# MAIN.net
KiCad netlist of a schematic drawn in Altium Designer
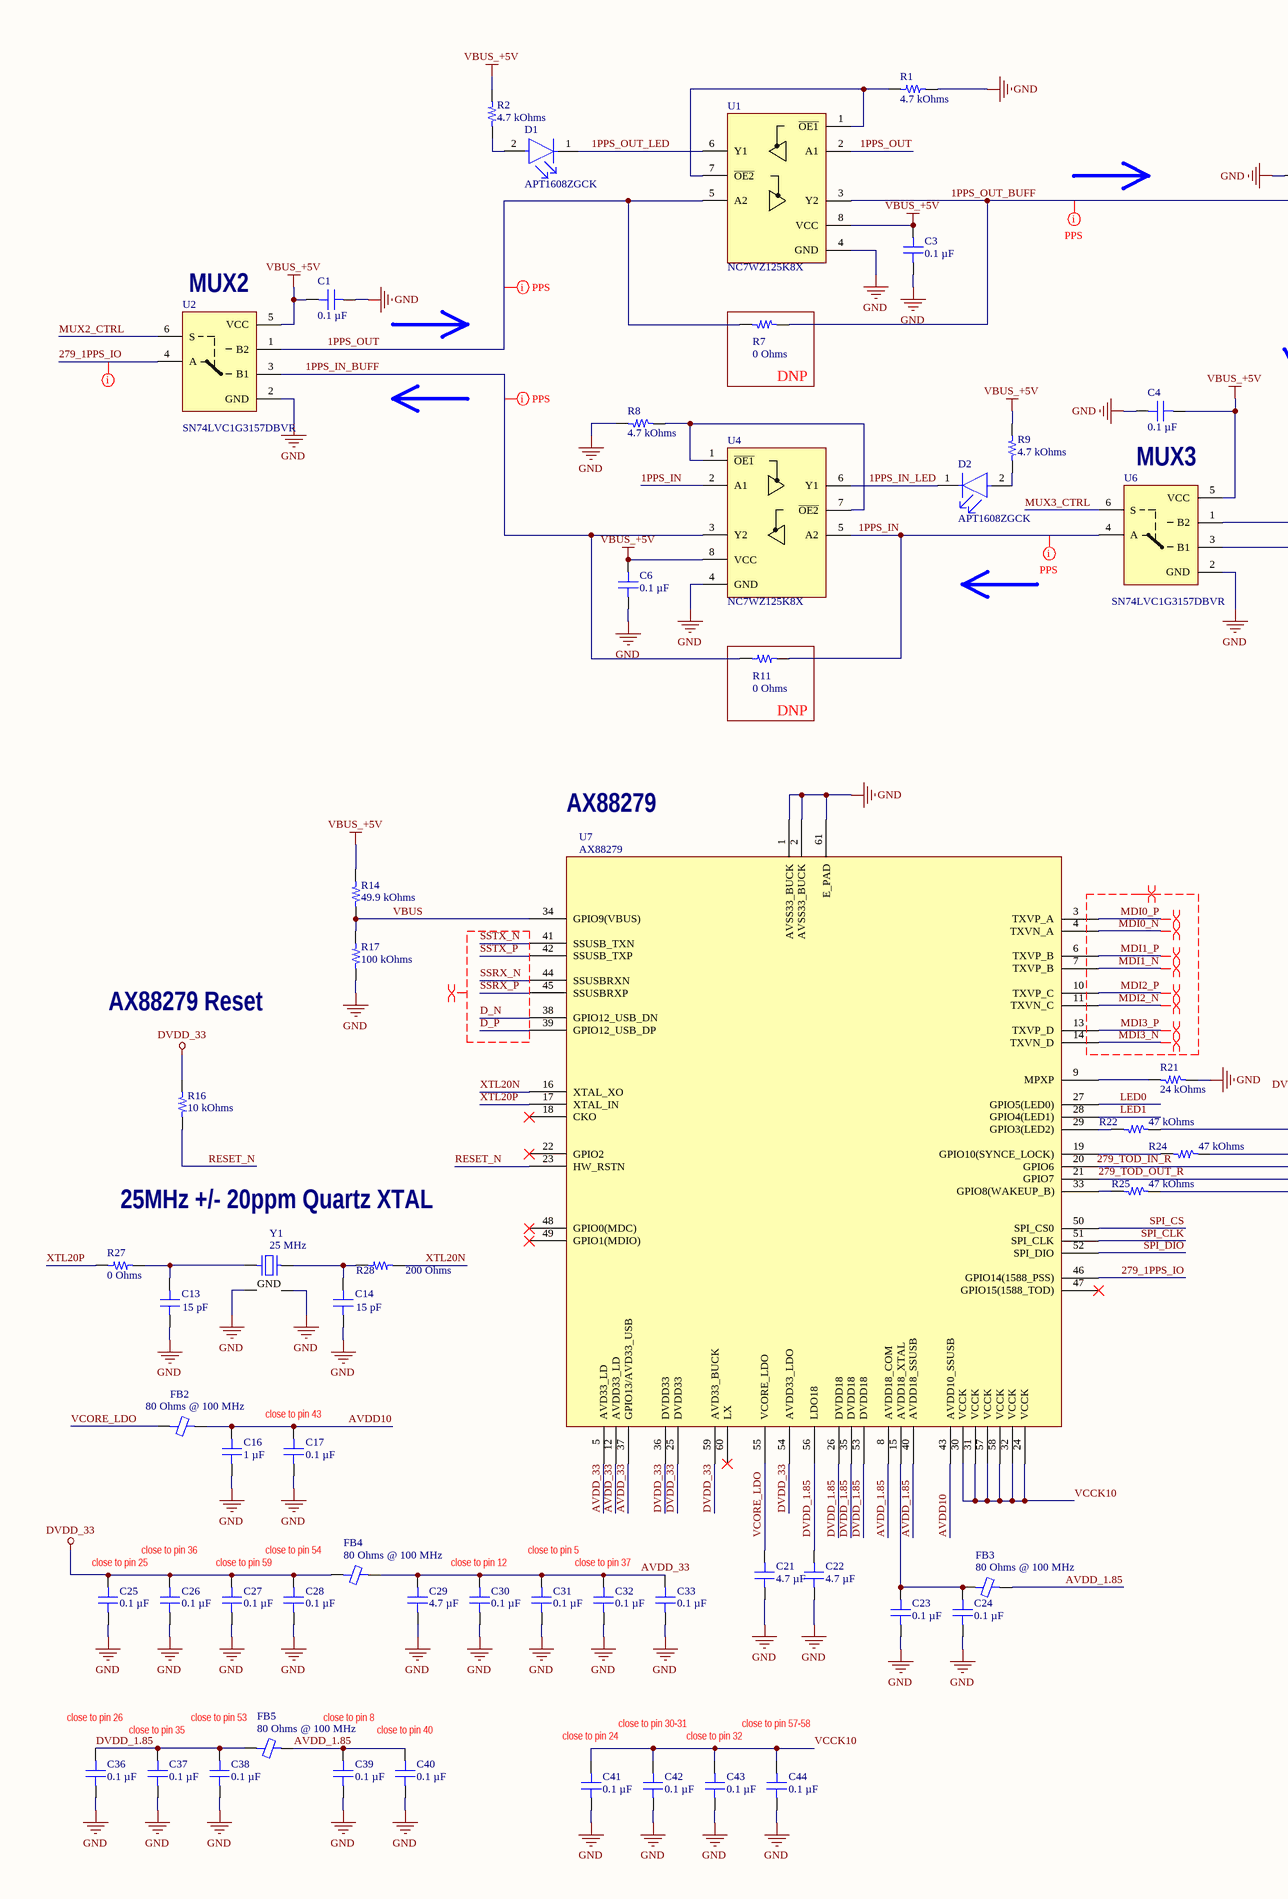
[diagram p0: MAIN.SchDoc, left]
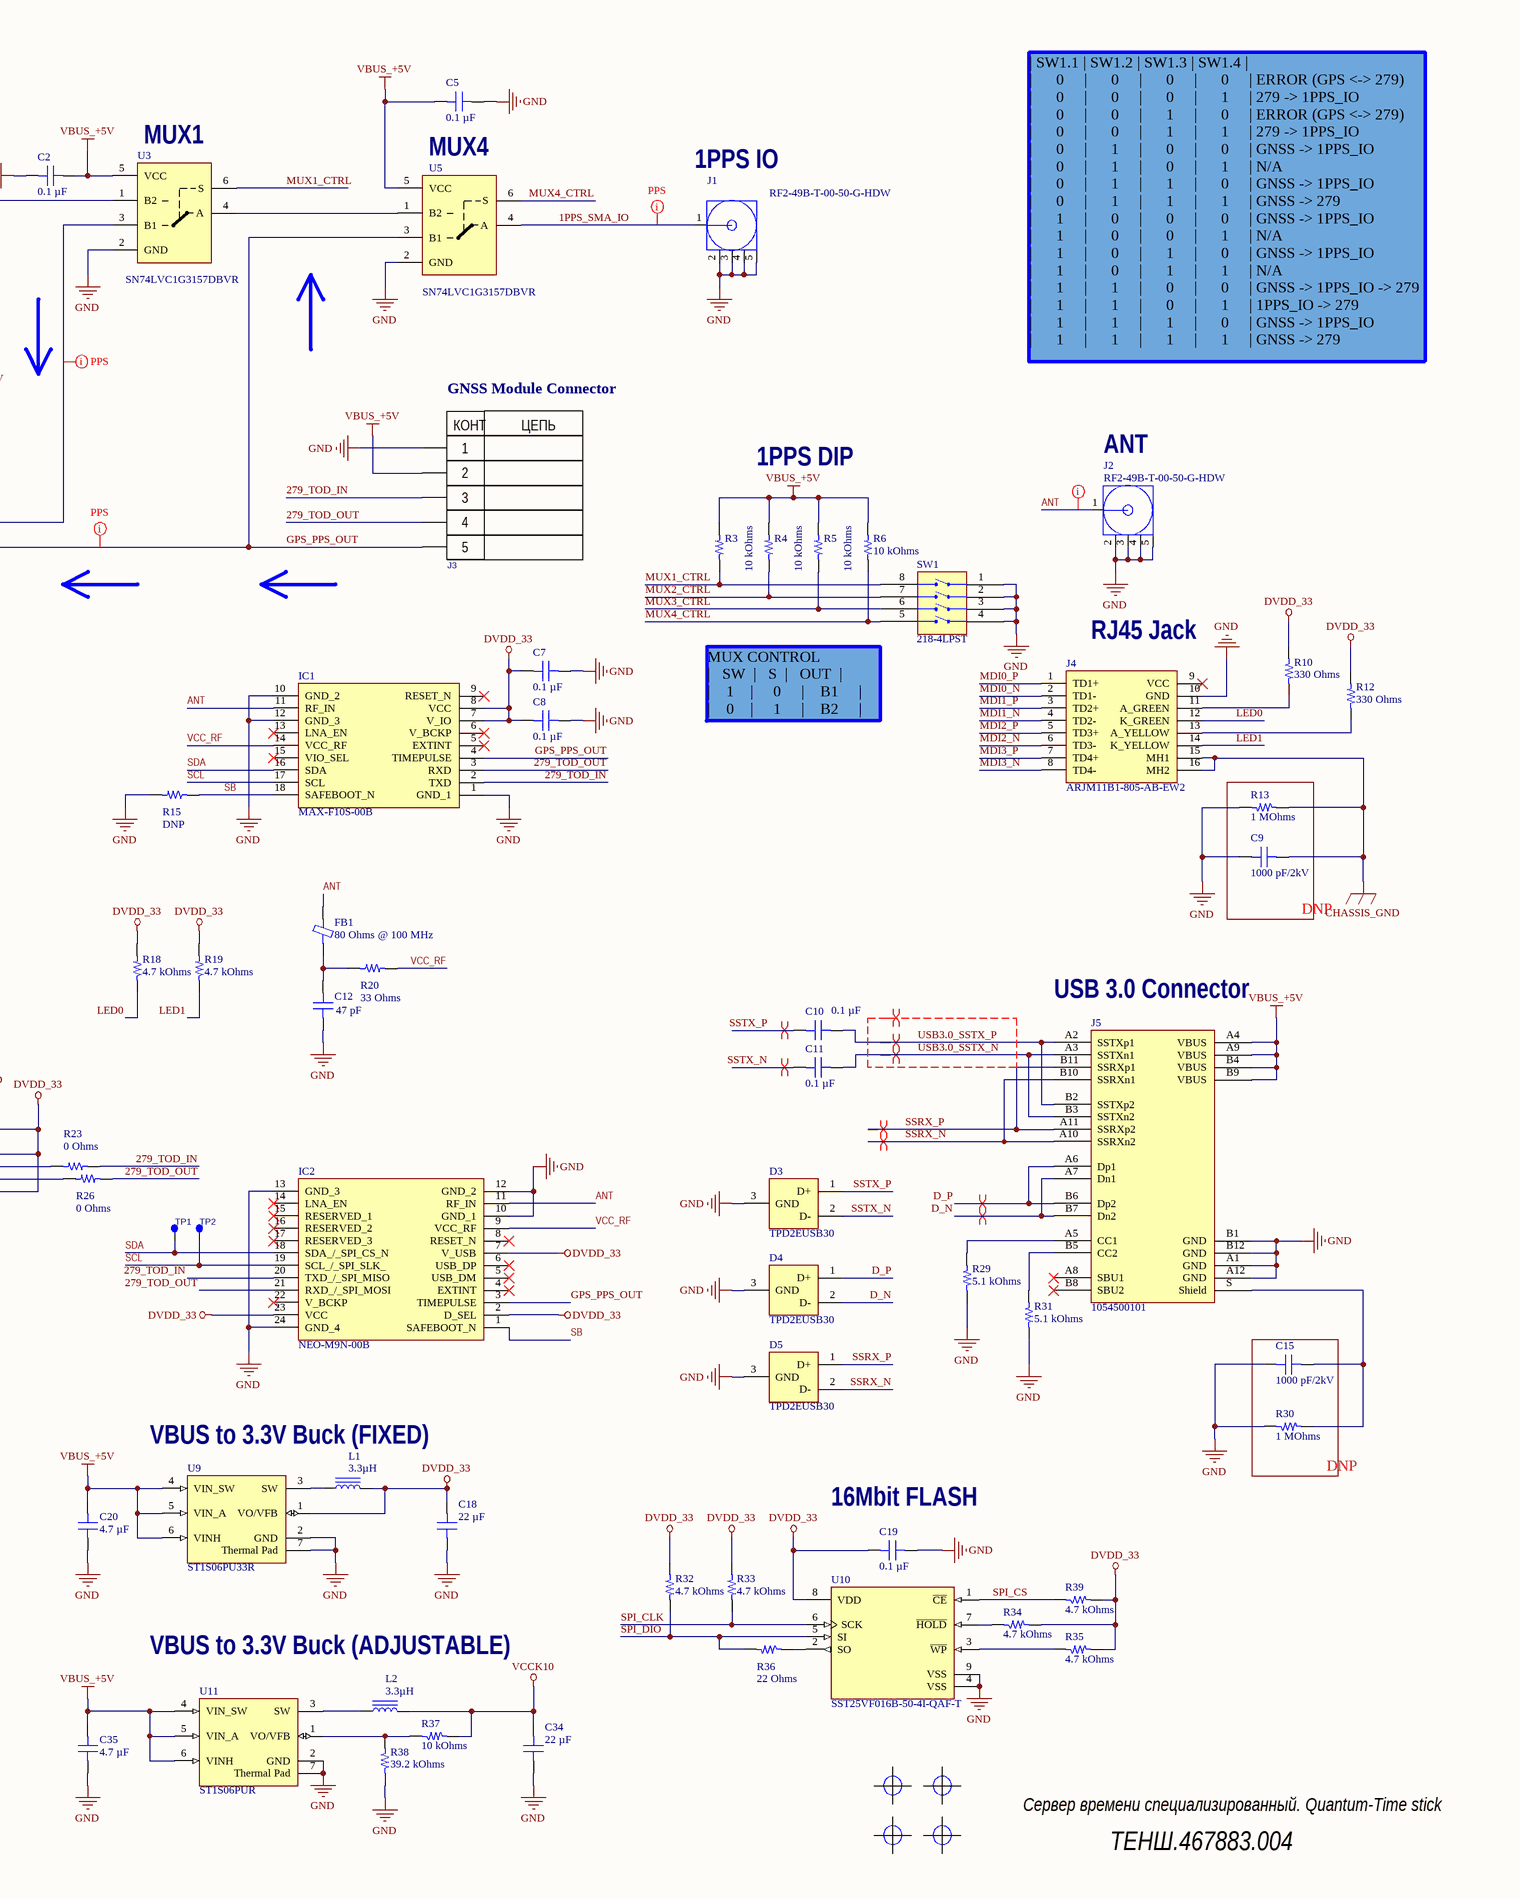
[diagram p1: MAIN.SchDoc, right]

(export (version "E")
  (design (tool "Eeschema 10.0.6"))
  (components
    (comp (ref "C1")
      (value "0.1 µF")
      (footprint "CAP 0402_1005")
      (description "CAP CER 0.1UF 10V X7R 0402")
      (fields (field (name "TOLERANCE") "±10%") (field (name "MANUFACTURER") "Yageo"))
      (libsource (lib "Celestial Altium Library - altium_library") (part "Capacitor"))
    )
    (comp (ref "C2")
      (value "0.1 µF")
      (footprint "CAP 0402_1005")
      (description "CAP CER 0.1UF 10V X7R 0402")
      (fields (field (name "TOLERANCE") "±10%") (field (name "MANUFACTURER") "Yageo"))
      (libsource (lib "Celestial Altium Library - altium_library") (part "Capacitor"))
    )
    (comp (ref "C3")
      (value "0.1 µF")
      (footprint "CAP 0402_1005")
      (description "CAP CER 0.1UF 10V X7R 0402")
      (fields (field (name "TOLERANCE") "±10%") (field (name "MANUFACTURER") "Yageo"))
      (libsource (lib "Celestial Altium Library - altium_library") (part "Capacitor"))
    )
    (comp (ref "C4")
      (value "0.1 µF")
      (footprint "CAP 0402_1005")
      (description "CAP CER 0.1UF 10V X7R 0402")
      (fields (field (name "TOLERANCE") "±10%") (field (name "MANUFACTURER") "Yageo"))
      (libsource (lib "Celestial Altium Library - altium_library") (part "Capacitor"))
    )
    (comp (ref "C5")
      (value "0.1 µF")
      (footprint "CAP 0402_1005")
      (description "CAP CER 0.1UF 10V X7R 0402")
      (fields (field (name "TOLERANCE") "±10%") (field (name "MANUFACTURER") "Yageo"))
      (libsource (lib "Celestial Altium Library - altium_library") (part "Capacitor"))
    )
    (comp (ref "C6")
      (value "0.1 µF")
      (footprint "CAP 0402_1005")
      (description "CAP CER 0.1UF 10V X7R 0402")
      (fields (field (name "TOLERANCE") "±10%") (field (name "MANUFACTURER") "Yageo"))
      (libsource (lib "Celestial Altium Library - altium_library") (part "Capacitor"))
    )
    (comp (ref "C7")
      (value "0.1 µF")
      (footprint "CAP 0402_1005")
      (description "CAP CER 0.1UF 10V X7R 0402")
      (fields (field (name "TOLERANCE") "±10%") (field (name "MANUFACTURER") "Yageo"))
      (libsource (lib "Celestial Altium Library - altium_library") (part "Capacitor"))
    )
    (comp (ref "C8")
      (value "0.1 µF")
      (footprint "CAP 0402_1005")
      (description "CAP CER 0.1UF 10V X7R 0402")
      (fields (field (name "TOLERANCE") "±10%") (field (name "MANUFACTURER") "Yageo"))
      (libsource (lib "Celestial Altium Library - altium_library") (part "Capacitor"))
    )
    (comp (ref "C9")
      (value "1000 pF/2kV")
      (footprint "CAP 1206_3216 - 0.8MM")
      (description "CAP CER 1000PF 2KV X7R 1206")
      (fields (field (name "PART NUMBER") "CC1206KKX7RDBB102") (field (name "MANUFACTURER") "Yageo"))
      (libsource (lib "Celestial Altium Library - altium_library") (part "Capacitor"))
    )
    (comp (ref "C10")
      (value "0.1 µF")
      (footprint "CAP 0402_1005")
      (description "CAP CER 0.1UF 10V X7R 0402")
      (fields (field (name "TOLERANCE") "±10%") (field (name "MANUFACTURER") "Yageo"))
      (libsource (lib "Celestial Altium Library - altium_library") (part "Capacitor"))
    )
    (comp (ref "C11")
      (value "0.1 µF")
      (footprint "CAP 0402_1005")
      (description "CAP CER 0.1UF 10V X7R 0402")
      (fields (field (name "TOLERANCE") "±10%") (field (name "MANUFACTURER") "Yageo"))
      (libsource (lib "Celestial Altium Library - altium_library") (part "Capacitor"))
    )
    (comp (ref "C12")
      (value "47 pF")
      (footprint "CAP 0402_1005")
      (description "CAP CER 47PF 50V C0G/NPO 0402")
      (fields (field (name "MANUFACTURER") "Yageo") (field (name "TOLERANCE") "±10%"))
      (libsource (lib "Celestial Altium Library - altium_library") (part "Capacitor"))
    )
    (comp (ref "C13")
      (value "15 pF")
      (footprint "CAP 0402_1005")
      (description "CAP CER 15PF 50V C0G/NPO 0402")
      (fields (field (name "MANUFACTURER") "Yageo") (field (name "TOLERANCE") "±10%"))
      (libsource (lib "Celestial Altium Library - altium_library") (part "Capacitor"))
    )
    (comp (ref "C14")
      (value "15 pF")
      (footprint "CAP 0402_1005")
      (description "CAP CER 15PF 50V C0G/NPO 0402")
      (fields (field (name "MANUFACTURER") "Yageo") (field (name "TOLERANCE") "±10%"))
      (libsource (lib "Celestial Altium Library - altium_library") (part "Capacitor"))
    )
    (comp (ref "C15")
      (value "1000 pF/2kV")
      (footprint "CAP 1206_3216 - 0.8MM")
      (description "CAP CER 1000PF 2KV X7R 1206")
      (fields (field (name "PART NUMBER") "CC1206KKX7RDBB102") (field (name "MANUFACTURER") "Yageo"))
      (libsource (lib "Celestial Altium Library - altium_library") (part "Capacitor"))
    )
    (comp (ref "C16")
      (value "1 µF")
      (footprint "CAP 0402_1005")
      (description "CAP CER 1UF 10V X5R 0402")
      (fields (field (name "TOLERANCE") "±10%") (field (name "MANUFACTURER") "Yageo"))
      (libsource (lib "Celestial Altium Library - altium_library") (part "Capacitor"))
    )
    (comp (ref "C17")
      (value "0.1 µF")
      (footprint "CAP 0402_1005")
      (description "CAP CER 0.1UF 10V X7R 0402")
      (fields (field (name "TOLERANCE") "±10%") (field (name "MANUFACTURER") "Yageo"))
      (libsource (lib "Celestial Altium Library - altium_library") (part "Capacitor"))
    )
    (comp (ref "C18")
      (value "22 µF")
      (footprint "CAP 0603_1608")
      (description "CAP CER 22UF 10V X5R 0603")
      (fields (field (name "MANUFACTURER") "Yageo") (field (name "TOLERANCE") "±20%"))
      (libsource (lib "Celestial Altium Library - altium_library") (part "Capacitor"))
    )
    (comp (ref "C19")
      (value "0.1 µF")
      (footprint "CAP 0402_1005")
      (description "CAP CER 0.1UF 10V X7R 0402")
      (fields (field (name "TOLERANCE") "±10%") (field (name "MANUFACTURER") "Yageo"))
      (libsource (lib "Celestial Altium Library - altium_library") (part "Capacitor"))
    )
    (comp (ref "C20")
      (value "4.7 µF")
      (footprint "CAP 0402_1005")
      (description "CAP CER 4.7UF 10V X5R 0402")
      (fields (field (name "TOLERANCE") "±20%") (field (name "MANUFACTURER") "Yageo"))
      (libsource (lib "Celestial Altium Library - altium_library") (part "Capacitor"))
    )
    (comp (ref "C21")
      (value "4.7 µF")
      (footprint "CAP 0402_1005")
      (description "CAP CER 4.7UF 10V X5R 0402")
      (fields (field (name "TOLERANCE") "±20%") (field (name "MANUFACTURER") "Yageo"))
      (libsource (lib "Celestial Altium Library - altium_library") (part "Capacitor"))
    )
    (comp (ref "C22")
      (value "4.7 µF")
      (footprint "CAP 0402_1005")
      (description "CAP CER 4.7UF 10V X5R 0402")
      (fields (field (name "TOLERANCE") "±20%") (field (name "MANUFACTURER") "Yageo"))
      (libsource (lib "Celestial Altium Library - altium_library") (part "Capacitor"))
    )
    (comp (ref "C23")
      (value "0.1 µF")
      (footprint "CAP 0402_1005")
      (description "CAP CER 0.1UF 10V X7R 0402")
      (fields (field (name "TOLERANCE") "±10%") (field (name "MANUFACTURER") "Yageo"))
      (libsource (lib "Celestial Altium Library - altium_library") (part "Capacitor"))
    )
    (comp (ref "C24")
      (value "0.1 µF")
      (footprint "CAP 0402_1005")
      (description "CAP CER 0.1UF 10V X7R 0402")
      (fields (field (name "TOLERANCE") "±10%") (field (name "MANUFACTURER") "Yageo"))
      (libsource (lib "Celestial Altium Library - altium_library") (part "Capacitor"))
    )
    (comp (ref "C25")
      (value "0.1 µF")
      (footprint "CAP 0402_1005")
      (description "CAP CER 0.1UF 10V X7R 0402")
      (fields (field (name "TOLERANCE") "±10%") (field (name "MANUFACTURER") "Yageo"))
      (libsource (lib "Celestial Altium Library - altium_library") (part "Capacitor"))
    )
    (comp (ref "C26")
      (value "0.1 µF")
      (footprint "CAP 0402_1005")
      (description "CAP CER 0.1UF 10V X7R 0402")
      (fields (field (name "TOLERANCE") "±10%") (field (name "MANUFACTURER") "Yageo"))
      (libsource (lib "Celestial Altium Library - altium_library") (part "Capacitor"))
    )
    (comp (ref "C27")
      (value "0.1 µF")
      (footprint "CAP 0402_1005")
      (description "CAP CER 0.1UF 10V X7R 0402")
      (fields (field (name "TOLERANCE") "±10%") (field (name "MANUFACTURER") "Yageo"))
      (libsource (lib "Celestial Altium Library - altium_library") (part "Capacitor"))
    )
    (comp (ref "C28")
      (value "0.1 µF")
      (footprint "CAP 0402_1005")
      (description "CAP CER 0.1UF 10V X7R 0402")
      (fields (field (name "TOLERANCE") "±10%") (field (name "MANUFACTURER") "Yageo"))
      (libsource (lib "Celestial Altium Library - altium_library") (part "Capacitor"))
    )
    (comp (ref "C29")
      (value "4.7 µF")
      (footprint "CAP 0402_1005")
      (description "CAP CER 4.7UF 10V X5R 0402")
      (fields (field (name "TOLERANCE") "±20%") (field (name "MANUFACTURER") "Yageo"))
      (libsource (lib "Celestial Altium Library - altium_library") (part "Capacitor"))
    )
    (comp (ref "C30")
      (value "0.1 µF")
      (footprint "CAP 0402_1005")
      (description "CAP CER 0.1UF 10V X7R 0402")
      (fields (field (name "TOLERANCE") "±10%") (field (name "MANUFACTURER") "Yageo"))
      (libsource (lib "Celestial Altium Library - altium_library") (part "Capacitor"))
    )
    (comp (ref "C31")
      (value "0.1 µF")
      (footprint "CAP 0402_1005")
      (description "CAP CER 0.1UF 10V X7R 0402")
      (fields (field (name "TOLERANCE") "±10%") (field (name "MANUFACTURER") "Yageo"))
      (libsource (lib "Celestial Altium Library - altium_library") (part "Capacitor"))
    )
    (comp (ref "C32")
      (value "0.1 µF")
      (footprint "CAP 0402_1005")
      (description "CAP CER 0.1UF 10V X7R 0402")
      (fields (field (name "TOLERANCE") "±10%") (field (name "MANUFACTURER") "Yageo"))
      (libsource (lib "Celestial Altium Library - altium_library") (part "Capacitor"))
    )
    (comp (ref "C33")
      (value "0.1 µF")
      (footprint "CAP 0402_1005")
      (description "CAP CER 0.1UF 10V X7R 0402")
      (fields (field (name "TOLERANCE") "±10%") (field (name "MANUFACTURER") "Yageo"))
      (libsource (lib "Celestial Altium Library - altium_library") (part "Capacitor"))
    )
    (comp (ref "C34")
      (value "22 µF")
      (footprint "CAP 0603_1608")
      (description "CAP CER 22UF 10V X5R 0603")
      (fields (field (name "MANUFACTURER") "Yageo") (field (name "TOLERANCE") "±20%"))
      (libsource (lib "Celestial Altium Library - altium_library") (part "Capacitor"))
    )
    (comp (ref "C35")
      (value "4.7 µF")
      (footprint "CAP 0402_1005")
      (description "CAP CER 4.7UF 10V X5R 0402")
      (fields (field (name "TOLERANCE") "±20%") (field (name "MANUFACTURER") "Yageo"))
      (libsource (lib "Celestial Altium Library - altium_library") (part "Capacitor"))
    )
    (comp (ref "C36")
      (value "0.1 µF")
      (footprint "CAP 0402_1005")
      (description "CAP CER 0.1UF 10V X7R 0402")
      (fields (field (name "TOLERANCE") "±10%") (field (name "MANUFACTURER") "Yageo"))
      (libsource (lib "Celestial Altium Library - altium_library") (part "Capacitor"))
    )
    (comp (ref "C37")
      (value "0.1 µF")
      (footprint "CAP 0402_1005")
      (description "CAP CER 0.1UF 10V X7R 0402")
      (fields (field (name "TOLERANCE") "±10%") (field (name "MANUFACTURER") "Yageo"))
      (libsource (lib "Celestial Altium Library - altium_library") (part "Capacitor"))
    )
    (comp (ref "C38")
      (value "0.1 µF")
      (footprint "CAP 0402_1005")
      (description "CAP CER 0.1UF 10V X7R 0402")
      (fields (field (name "TOLERANCE") "±10%") (field (name "MANUFACTURER") "Yageo"))
      (libsource (lib "Celestial Altium Library - altium_library") (part "Capacitor"))
    )
    (comp (ref "C39")
      (value "0.1 µF")
      (footprint "CAP 0402_1005")
      (description "CAP CER 0.1UF 10V X7R 0402")
      (fields (field (name "TOLERANCE") "±10%") (field (name "MANUFACTURER") "Yageo"))
      (libsource (lib "Celestial Altium Library - altium_library") (part "Capacitor"))
    )
    (comp (ref "C40")
      (value "0.1 µF")
      (footprint "CAP 0402_1005")
      (description "CAP CER 0.1UF 10V X7R 0402")
      (fields (field (name "TOLERANCE") "±10%") (field (name "MANUFACTURER") "Yageo"))
      (libsource (lib "Celestial Altium Library - altium_library") (part "Capacitor"))
    )
    (comp (ref "C41")
      (value "0.1 µF")
      (footprint "CAP 0402_1005")
      (description "CAP CER 0.1UF 10V X7R 0402")
      (fields (field (name "TOLERANCE") "±10%") (field (name "MANUFACTURER") "Yageo"))
      (libsource (lib "Celestial Altium Library - altium_library") (part "Capacitor"))
    )
    (comp (ref "C42")
      (value "0.1 µF")
      (footprint "CAP 0402_1005")
      (description "CAP CER 0.1UF 10V X7R 0402")
      (fields (field (name "TOLERANCE") "±10%") (field (name "MANUFACTURER") "Yageo"))
      (libsource (lib "Celestial Altium Library - altium_library") (part "Capacitor"))
    )
    (comp (ref "C43")
      (value "0.1 µF")
      (footprint "CAP 0402_1005")
      (description "CAP CER 0.1UF 10V X7R 0402")
      (fields (field (name "TOLERANCE") "±10%") (field (name "MANUFACTURER") "Yageo"))
      (libsource (lib "Celestial Altium Library - altium_library") (part "Capacitor"))
    )
    (comp (ref "C44")
      (value "0.1 µF")
      (footprint "CAP 0402_1005")
      (description "CAP CER 0.1UF 10V X7R 0402")
      (fields (field (name "TOLERANCE") "±10%") (field (name "MANUFACTURER") "Yageo"))
      (libsource (lib "Celestial Altium Library - altium_library") (part "Capacitor"))
    )
    (comp (ref "D1")
      (value "APT1608ZGCK")
      (footprint "FP-APT1608ZGCK-MFG")
      (description "LED GREEN CLEAR CHIP SMD")
      (fields (field (name "MANUFACTURER") "Kingbright"))
      (libsource (lib "Altium Content Vault") (part "8706943c75ba83719d021d2fdc84c58"))
    )
    (comp (ref "D2")
      (value "APT1608ZGCK")
      (footprint "FP-APT1608ZGCK-MFG")
      (description "LED GREEN CLEAR CHIP SMD")
      (fields (field (name "MANUFACTURER") "Kingbright"))
      (libsource (lib "Altium Content Vault") (part "8706943c75ba83719d021d2fdc84c58"))
    )
    (comp (ref "D3")
      (value "TPD2EUSB30")
      (footprint "SamacSys:SOT35P100X50-3N")
      (description "TVS DIODE 3.6VWM 8VC SOT3")
      (fields
        (field (name "MANUFACTURER_PART_NUMBER") "TPD2EUSB30ADRTR")
        (field (name "MOUSER PART NUMBER") "595-TPD2EUSB30ADRTR")
      )
      (libsource (lib "SamacSys") (part "TPD2EUSB30ADRTR"))
    )
    (comp (ref "D4")
      (value "TPD2EUSB30")
      (footprint "SamacSys:SOT35P100X50-3N")
      (description "TVS DIODE 3.6VWM 8VC SOT3")
      (fields
        (field (name "MANUFACTURER_PART_NUMBER") "TPD2EUSB30ADRTR")
        (field (name "MOUSER PART NUMBER") "595-TPD2EUSB30ADRTR")
      )
      (libsource (lib "SamacSys") (part "TPD2EUSB30ADRTR"))
    )
    (comp (ref "D5")
      (value "TPD2EUSB30")
      (footprint "SamacSys:SOT35P100X50-3N")
      (description "TVS DIODE 3.6VWM 8VC SOT3")
      (fields
        (field (name "MANUFACTURER_PART_NUMBER") "TPD2EUSB30ADRTR")
        (field (name "MOUSER PART NUMBER") "595-TPD2EUSB30ADRTR")
      )
      (libsource (lib "SamacSys") (part "TPD2EUSB30ADRTR"))
    )
    (comp (ref "FB1")
      (value "80 Ohms @ 100 MHz")
      (footprint "FER 0402_1005")
      (description "FERRITE BEAD 80 OHM 0402 1LN")
      (fields
        (field (name "MANUFACTURER") "Murata Electronics")
        (field (name "PART NUMBER") "BLM15PD800SN1D")
      )
      (libsource (lib "Celestial Altium Library - altium_library") (part "Ferrite Chip"))
    )
    (comp (ref "FB2")
      (value "80 Ohms @ 100 MHz")
      (footprint "FER 0402_1005")
      (description "FERRITE BEAD 80 OHM 0402 1LN")
      (fields
        (field (name "MANUFACTURER") "Murata Electronics")
        (field (name "PART NUMBER") "BLM15PD800SN1D")
      )
      (libsource (lib "Celestial Altium Library - altium_library") (part "Ferrite Chip"))
    )
    (comp (ref "FB3")
      (value "80 Ohms @ 100 MHz")
      (footprint "FER 0402_1005")
      (description "FERRITE BEAD 80 OHM 0402 1LN")
      (fields
        (field (name "MANUFACTURER") "Murata Electronics")
        (field (name "PART NUMBER") "BLM15PD800SN1D")
      )
      (libsource (lib "Celestial Altium Library - altium_library") (part "Ferrite Chip"))
    )
    (comp (ref "FB4")
      (value "80 Ohms @ 100 MHz")
      (footprint "FER 0402_1005")
      (description "FERRITE BEAD 80 OHM 0402 1LN")
      (fields
        (field (name "MANUFACTURER") "Murata Electronics")
        (field (name "PART NUMBER") "BLM15PD800SN1D")
      )
      (libsource (lib "Celestial Altium Library - altium_library") (part "Ferrite Chip"))
    )
    (comp (ref "FB5")
      (value "80 Ohms @ 100 MHz")
      (footprint "FER 0402_1005")
      (description "FERRITE BEAD 80 OHM 0402 1LN")
      (fields
        (field (name "MANUFACTURER") "Murata Electronics")
        (field (name "PART NUMBER") "BLM15PD800SN1D")
      )
      (libsource (lib "Celestial Altium Library - altium_library") (part "Ferrite Chip"))
    )
    (comp (ref "IC1")
      (value "MAX-F10S-00B")
      (footprint "SamacSys:MAXF10S00B")
      (description "Integrated Circuit")
      (libsource (lib "SamacSys") (part "MAX-F10S-00B"))
    )
    (comp (ref "IC2")
      (value "NEO-M9N-00B")
      (footprint "SamacSys:NEOM9N00B")
      (description "Integrated Circuit")
      (fields (field (name "MOUSER PART NUMBER") "377-NEO-M9N-00B"))
      (libsource (lib "SamacSys") (part "NEO-M9N-00B"))
    )
    (comp (ref "J1")
      (value "RF2-49B-T-00-50-G-HDW")
      (footprint "SamacSys:RF249BT0050GHDW")
      (description "Connector")
      (libsource (lib "SamacSys") (part "RF2-49B-T-00-50-G-HDW"))
    )
    (comp (ref "J2")
      (value "RF2-49B-T-00-50-G-HDW")
      (footprint "SamacSys:RF249BT0050GHDW")
      (description "Connector")
      (libsource (lib "SamacSys") (part "RF2-49B-T-00-50-G-HDW"))
    )
    (comp (ref "J3")
      (value "PBS-5")
      (footprint "SamacSys:PBS-5")
      (description "Connector")
      (fields (field (name "MANUFACTURER") "Connfly") (field (name "PART NUMBER") "PBD-5"))
      (libsource (lib "SamacSys") (part "PBS-5"))
    )
    (comp (ref "J4")
      (value "ARJM11B1-805-AB-EW2")
      (footprint "SamacSys:ARJM11B1805ABEW2")
      (description "Connector")
      (fields (field (name "MOUSER PART NUMBER") "815-RJM11B1805ABEW2"))
      (libsource (lib "SamacSys") (part "ARJM11B1-805-AB-EW2"))
    )
    (comp (ref "J5")
      (value "1054500101")
      (footprint "Molex 1054500101")
      (description "CONN RCP USB3.1 TYPEC 24P SMD RA")
      (fields (field (name "MANUFACTURER") "Molex"))
      (libsource (lib "Celestial Altium Library - altium_library") (part "USB 3.0 Type C"))
    )
    (comp (ref "L1")
      (value "3.3µH")
      (footprint "IND 1008_2520")
      (description "FIXED IND 3.3UH 1.2A 100 MOHM")
      (fields (field (name "TOLERANCE") "±20%") (field (name "MANUFACTURER") "Murata Electronics"))
      (libsource (lib "Celestial Altium Library - altium_library") (part "Inductor"))
    )
    (comp (ref "L2")
      (value "3.3µH")
      (footprint "IND 1008_2520")
      (description "FIXED IND 3.3UH 1.2A 100 MOHM")
      (fields (field (name "TOLERANCE") "±20%") (field (name "MANUFACTURER") "Murata Electronics"))
      (libsource (lib "Celestial Altium Library - altium_library") (part "Inductor"))
    )
    (comp (ref "MNT1")
      (value "MOUNT_HOLE")
      (footprint "SamacSys:MOUNT_3mm")
      (description "Mount hole")
      (libsource (lib "SamacSys") (part "MOUNT_HOLE"))
    )
    (comp (ref "MNT2")
      (value "MOUNT_HOLE")
      (footprint "SamacSys:MOUNT_3mm")
      (description "Mount hole")
      (libsource (lib "SamacSys") (part "MOUNT_HOLE"))
    )
    (comp (ref "MNT3")
      (value "MOUNT_HOLE")
      (footprint "SamacSys:MOUNT_3mm")
      (description "Mount hole")
      (libsource (lib "SamacSys") (part "MOUNT_HOLE"))
    )
    (comp (ref "MNT4")
      (value "MOUNT_HOLE")
      (footprint "SamacSys:MOUNT_3mm")
      (description "Mount hole")
      (libsource (lib "SamacSys") (part "MOUNT_HOLE"))
    )
    (comp (ref "R1")
      (value "4.7 kOhms")
      (footprint "YAGEO RES 0402_1005")
      (description "RES 4.7K OHM 1% 1/16W 0402")
      (fields (field (name "TOLERANCE") "±1%") (field (name "MANUFACTURER") "Yageo"))
      (libsource (lib "Celestial Altium Library - altium_library") (part "Resistor"))
    )
    (comp (ref "R2")
      (value "4.7 kOhms")
      (footprint "YAGEO RES 0402_1005")
      (description "RES 4.7K OHM 1% 1/16W 0402")
      (fields (field (name "TOLERANCE") "±1%") (field (name "MANUFACTURER") "Yageo"))
      (libsource (lib "Celestial Altium Library - altium_library") (part "Resistor"))
    )
    (comp (ref "R3")
      (value "10 kOhms")
      (footprint "YAGEO RES 0402_1005")
      (description "RES 10K OHM 1% 1/16W 0402")
      (fields (field (name "TOLERANCE") "±1%") (field (name "MANUFACTURER") "Yageo"))
      (libsource (lib "Celestial Altium Library - altium_library") (part "Resistor"))
    )
    (comp (ref "R4")
      (value "10 kOhms")
      (footprint "YAGEO RES 0402_1005")
      (description "RES 10K OHM 1% 1/16W 0402")
      (fields (field (name "TOLERANCE") "±1%") (field (name "MANUFACTURER") "Yageo"))
      (libsource (lib "Celestial Altium Library - altium_library") (part "Resistor"))
    )
    (comp (ref "R5")
      (value "10 kOhms")
      (footprint "YAGEO RES 0402_1005")
      (description "RES 10K OHM 1% 1/16W 0402")
      (fields (field (name "TOLERANCE") "±1%") (field (name "MANUFACTURER") "Yageo"))
      (libsource (lib "Celestial Altium Library - altium_library") (part "Resistor"))
    )
    (comp (ref "R6")
      (value "10 kOhms")
      (footprint "YAGEO RES 0402_1005")
      (description "RES 10K OHM 1% 1/16W 0402")
      (fields (field (name "TOLERANCE") "±1%") (field (name "MANUFACTURER") "Yageo"))
      (libsource (lib "Celestial Altium Library - altium_library") (part "Resistor"))
    )
    (comp (ref "R7")
      (value "0 Ohms")
      (footprint "YAGEO RES 0402_1005")
      (description "RES 0 OHM JUMPER 1/16W 0402")
      (fields (field (name "TOLERANCE") "Jumper") (field (name "MANUFACTURER") "Yageo"))
      (libsource (lib "Celestial Altium Library - altium_library") (part "Resistor"))
    )
    (comp (ref "R8")
      (value "4.7 kOhms")
      (footprint "YAGEO RES 0402_1005")
      (description "RES 4.7K OHM 1% 1/16W 0402")
      (fields (field (name "TOLERANCE") "±1%") (field (name "MANUFACTURER") "Yageo"))
      (libsource (lib "Celestial Altium Library - altium_library") (part "Resistor"))
    )
    (comp (ref "R9")
      (value "4.7 kOhms")
      (footprint "YAGEO RES 0402_1005")
      (description "RES 4.7K OHM 1% 1/16W 0402")
      (fields (field (name "TOLERANCE") "±1%") (field (name "MANUFACTURER") "Yageo"))
      (libsource (lib "Celestial Altium Library - altium_library") (part "Resistor"))
    )
    (comp (ref "R10")
      (value "330 Ohms")
      (footprint "YAGEO RES 0402_1005")
      (description "RES 330 OHM 1% 1/16W 0402")
      (fields (field (name "TOLERANCE") "±1%") (field (name "MANUFACTURER") "Yageo"))
      (libsource (lib "Celestial Altium Library - altium_library") (part "Resistor"))
    )
    (comp (ref "R11")
      (value "0 Ohms")
      (footprint "YAGEO RES 0402_1005")
      (description "RES 0 OHM JUMPER 1/16W 0402")
      (fields (field (name "TOLERANCE") "Jumper") (field (name "MANUFACTURER") "Yageo"))
      (libsource (lib "Celestial Altium Library - altium_library") (part "Resistor"))
    )
    (comp (ref "R12")
      (value "330 Ohms")
      (footprint "YAGEO RES 0402_1005")
      (description "RES 330 OHM 1% 1/16W 0402")
      (fields (field (name "TOLERANCE") "±1%") (field (name "MANUFACTURER") "Yageo"))
      (libsource (lib "Celestial Altium Library - altium_library") (part "Resistor"))
    )
    (comp (ref "R13")
      (value "1 MOhms")
      (footprint "YAGEO RES 0402_1005")
      (description "RES 1M OHM 1% 1/16W 0402")
      (fields (field (name "TOLERANCE") "±1%") (field (name "MANUFACTURER") "Yageo"))
      (libsource (lib "Celestial Altium Library - altium_library") (part "Resistor"))
    )
    (comp (ref "R14")
      (value "49.9 kOhms")
      (footprint "YAGEO RES 0402_1005")
      (description "RES 49.9K OHM 1% 1/16W 0402")
      (fields (field (name "TOLERANCE") "±1%") (field (name "MANUFACTURER") "Yageo"))
      (libsource (lib "Celestial Altium Library - altium_library") (part "Resistor"))
    )
    (comp (ref "R15")
      (value "DNP")
      (footprint "YAGEO RES 0402_1005")
      (description "RES 0 OHM JUMPER 1/16W 0402")
      (fields (field (name "TOLERANCE") "Jumper") (field (name "MANUFACTURER") "Yageo"))
      (libsource (lib "Celestial Altium Library - altium_library") (part "Resistor"))
    )
    (comp (ref "R16")
      (value "10 kOhms")
      (footprint "YAGEO RES 0402_1005")
      (description "RES 10K OHM 1% 1/16W 0402")
      (fields (field (name "TOLERANCE") "±1%") (field (name "MANUFACTURER") "Yageo"))
      (libsource (lib "Celestial Altium Library - altium_library") (part "Resistor"))
    )
    (comp (ref "R17")
      (value "100 kOhms")
      (footprint "YAGEO RES 0402_1005")
      (description "RES 100K OHM 1% 1/16W 0402")
      (fields (field (name "TOLERANCE") "±1%") (field (name "MANUFACTURER") "Yageo"))
      (libsource (lib "Celestial Altium Library - altium_library") (part "Resistor"))
    )
    (comp (ref "R18")
      (value "4.7 kOhms")
      (footprint "YAGEO RES 0402_1005")
      (description "RES 4.7K OHM 1% 1/16W 0402")
      (fields (field (name "TOLERANCE") "±1%") (field (name "MANUFACTURER") "Yageo"))
      (libsource (lib "Celestial Altium Library - altium_library") (part "Resistor"))
    )
    (comp (ref "R19")
      (value "4.7 kOhms")
      (footprint "YAGEO RES 0402_1005")
      (description "RES 4.7K OHM 1% 1/16W 0402")
      (fields (field (name "TOLERANCE") "±1%") (field (name "MANUFACTURER") "Yageo"))
      (libsource (lib "Celestial Altium Library - altium_library") (part "Resistor"))
    )
    (comp (ref "R20")
      (value "33 Ohms")
      (footprint "YAGEO RES 0402_1005")
      (description "RES 33 OHM 1% 1/16W 0402")
      (fields (field (name "TOLERANCE") "±1%") (field (name "MANUFACTURER") "Yageo"))
      (libsource (lib "Celestial Altium Library - altium_library") (part "Resistor"))
    )
    (comp (ref "R21")
      (value "24 kOhms")
      (footprint "YAGEO RES 0402_1005")
      (description "RES 24K OHM 1% 1/16W 0402")
      (fields (field (name "TOLERANCE") "±1%") (field (name "MANUFACTURER") "Yageo"))
      (libsource (lib "Celestial Altium Library - altium_library") (part "Resistor"))
    )
    (comp (ref "R22")
      (value "47 kOhms")
      (footprint "YAGEO RES 0402_1005")
      (description "RES 47K OHM 1% 1/16W 0402")
      (fields (field (name "TOLERANCE") "±1%") (field (name "MANUFACTURER") "Yageo"))
      (libsource (lib "Celestial Altium Library - altium_library") (part "Resistor"))
    )
    (comp (ref "R23")
      (value "0 Ohms")
      (footprint "YAGEO RES 0402_1005")
      (description "RES 0 OHM JUMPER 1/16W 0402")
      (fields (field (name "TOLERANCE") "Jumper") (field (name "MANUFACTURER") "Yageo"))
      (libsource (lib "Celestial Altium Library - altium_library") (part "Resistor"))
    )
    (comp (ref "R24")
      (value "47 kOhms")
      (footprint "YAGEO RES 0402_1005")
      (description "RES 47K OHM 1% 1/16W 0402")
      (fields (field (name "TOLERANCE") "±1%") (field (name "MANUFACTURER") "Yageo"))
      (libsource (lib "Celestial Altium Library - altium_library") (part "Resistor"))
    )
    (comp (ref "R25")
      (value "47 kOhms")
      (footprint "YAGEO RES 0402_1005")
      (description "RES 47K OHM 1% 1/16W 0402")
      (fields (field (name "TOLERANCE") "±1%") (field (name "MANUFACTURER") "Yageo"))
      (libsource (lib "Celestial Altium Library - altium_library") (part "Resistor"))
    )
    (comp (ref "R26")
      (value "0 Ohms")
      (footprint "YAGEO RES 0402_1005")
      (description "RES 0 OHM JUMPER 1/16W 0402")
      (fields (field (name "TOLERANCE") "Jumper") (field (name "MANUFACTURER") "Yageo"))
      (libsource (lib "Celestial Altium Library - altium_library") (part "Resistor"))
    )
    (comp (ref "R27")
      (value "0 Ohms")
      (footprint "YAGEO RES 0402_1005")
      (description "RES 0 OHM JUMPER 1/16W 0402")
      (fields (field (name "TOLERANCE") "Jumper") (field (name "MANUFACTURER") "Yageo"))
      (libsource (lib "Celestial Altium Library - altium_library") (part "Resistor"))
    )
    (comp (ref "R28")
      (value "200 Ohms")
      (footprint "YAGEO RES 0402_1005")
      (description "RES 200 OHM 1% 1/16W 0402")
      (fields (field (name "MANUFACTURER") "Yageo") (field (name "PART NUMBER") "RC0402FR-07200RL"))
      (libsource (lib "Celestial Altium Library - altium_library") (part "Resistor"))
    )
    (comp (ref "R29")
      (value "5.1 kOhms")
      (footprint "YAGEO RES 0402_1005")
      (description "RES 5.1K OHM 1% 1/16W 0402")
      (fields (field (name "TOLERANCE") "±1%") (field (name "MANUFACTURER") "Yageo"))
      (libsource (lib "Celestial Altium Library - altium_library") (part "Resistor"))
    )
    (comp (ref "R30")
      (value "1 MOhms")
      (footprint "YAGEO RES 0402_1005")
      (description "RES 1M OHM 1% 1/16W 0402")
      (fields (field (name "TOLERANCE") "±1%") (field (name "MANUFACTURER") "Yageo"))
      (libsource (lib "Celestial Altium Library - altium_library") (part "Resistor"))
    )
    (comp (ref "R31")
      (value "5.1 kOhms")
      (footprint "YAGEO RES 0402_1005")
      (description "RES 5.1K OHM 1% 1/16W 0402")
      (fields (field (name "TOLERANCE") "±1%") (field (name "MANUFACTURER") "Yageo"))
      (libsource (lib "Celestial Altium Library - altium_library") (part "Resistor"))
    )
    (comp (ref "R32")
      (value "4.7 kOhms")
      (footprint "YAGEO RES 0402_1005")
      (description "RES 4.7K OHM 1% 1/16W 0402")
      (fields (field (name "TOLERANCE") "±1%") (field (name "MANUFACTURER") "Yageo"))
      (libsource (lib "Celestial Altium Library - altium_library") (part "Resistor"))
    )
    (comp (ref "R33")
      (value "4.7 kOhms")
      (footprint "YAGEO RES 0402_1005")
      (description "RES 4.7K OHM 1% 1/16W 0402")
      (fields (field (name "TOLERANCE") "±1%") (field (name "MANUFACTURER") "Yageo"))
      (libsource (lib "Celestial Altium Library - altium_library") (part "Resistor"))
    )
    (comp (ref "R34")
      (value "4.7 kOhms")
      (footprint "YAGEO RES 0402_1005")
      (description "RES 4.7K OHM 1% 1/16W 0402")
      (fields (field (name "TOLERANCE") "±1%") (field (name "MANUFACTURER") "Yageo"))
      (libsource (lib "Celestial Altium Library - altium_library") (part "Resistor"))
    )
    (comp (ref "R35")
      (value "4.7 kOhms")
      (footprint "YAGEO RES 0402_1005")
      (description "RES 4.7K OHM 1% 1/16W 0402")
      (fields (field (name "TOLERANCE") "±1%") (field (name "MANUFACTURER") "Yageo"))
      (libsource (lib "Celestial Altium Library - altium_library") (part "Resistor"))
    )
    (comp (ref "R36")
      (value "22 Ohms")
      (footprint "YAGEO RES 0402_1005")
      (description "RES 22 OHM 1% 1/16W 0402")
      (fields (field (name "TOLERANCE") "±1%") (field (name "MANUFACTURER") "Yageo"))
      (libsource (lib "Celestial Altium Library - altium_library") (part "Resistor"))
    )
    (comp (ref "R37")
      (value "10 kOhms")
      (footprint "YAGEO RES 0402_1005")
      (description "RES 10K OHM 1% 1/16W 0402")
      (fields (field (name "TOLERANCE") "±1%") (field (name "MANUFACTURER") "Yageo"))
      (libsource (lib "Celestial Altium Library - altium_library") (part "Resistor"))
    )
    (comp (ref "R38")
      (value "39.2 kOhms")
      (footprint "YAGEO RES 0402_1005")
      (description "RES 39.2K OHM 1% 1/16W 0402")
      (fields (field (name "TOLERANCE") "±1%") (field (name "MANUFACTURER") "Yageo"))
      (libsource (lib "Celestial Altium Library - altium_library") (part "Resistor"))
    )
    (comp (ref "R39")
      (value "4.7 kOhms")
      (footprint "YAGEO RES 0402_1005")
      (description "RES 4.7K OHM 1% 1/16W 0402")
      (fields (field (name "TOLERANCE") "±1%") (field (name "MANUFACTURER") "Yageo"))
      (libsource (lib "Celestial Altium Library - altium_library") (part "Resistor"))
    )
    (comp (ref "SW1")
      (value "218-4LPST")
      (footprint "CTS 218-4LPJ")
      (description "SWITCH SLIDE DIP SPST 25MA 24V")
      (fields (field (name "MANUFACTURER") "CTS Electrocomponents"))
      (libsource (lib "Celestial Altium Library - altium_library") (part "DIP SW 4P"))
    )
    (comp (ref "TP1")
      (value "PAD_TEST")
      (footprint "Samacsys:PAD_TEST")
      (description "Test Point")
      (fields (field (name "TOLERANCE") "{Tolerance}") (field (name "MANUFACTURER") "{Manufacturer}"))
      (libsource (lib "SamacSys") (part "PAD_TEST"))
    )
    (comp (ref "TP2")
      (value "PAD_TEST")
      (footprint "Samacsys:PAD_TEST")
      (description "Test Point")
      (fields (field (name "TOLERANCE") "{Tolerance}") (field (name "MANUFACTURER") "{Manufacturer}"))
      (libsource (lib "SamacSys") (part "PAD_TEST"))
    )
    (comp (ref "U1")
      (value "NC7WZ125K8X")
      (footprint "SamacSys:SOP50P310X90-8N")
      (description "Integrated Circuit")
      (libsource (lib "") (part "NC7WZ125K8X_1"))
    )
    (comp (ref "U2")
      (value "SN74LVC1G3157DBVR")
      (footprint "SamacSys:SOT95P280X145-6N")
      (description "Integrated Circuit")
      (fields (field (name "MOUSER PART NUMBER") "595-SN74LVC1G3157DBV"))
      (libsource (lib "SamacSys") (part "SN74LVC1G3157DBVR"))
    )
    (comp (ref "U3")
      (value "SN74LVC1G3157DBVR")
      (footprint "SamacSys:SOT95P280X145-6N")
      (description "Integrated Circuit")
      (fields (field (name "MOUSER PART NUMBER") "595-SN74LVC1G3157DBV"))
      (libsource (lib "") (part "SN74LVC1G3157DBVR_1"))
    )
    (comp (ref "U4")
      (value "NC7WZ125K8X")
      (footprint "SamacSys:SOP50P310X90-8N")
      (description "Integrated Circuit")
      (libsource (lib "SamacSys") (part "NC7WZ125K8X"))
    )
    (comp (ref "U5")
      (value "SN74LVC1G3157DBVR")
      (footprint "SamacSys:SOT95P280X145-6N")
      (description "Integrated Circuit")
      (fields (field (name "MOUSER PART NUMBER") "595-SN74LVC1G3157DBV"))
      (libsource (lib "") (part "SN74LVC1G3157DBVR_1"))
    )
    (comp (ref "U6")
      (value "SN74LVC1G3157DBVR")
      (footprint "SamacSys:SOT95P280X145-6N")
      (description "Integrated Circuit")
      (fields (field (name "MOUSER PART NUMBER") "595-SN74LVC1G3157DBV"))
      (libsource (lib "SamacSys") (part "SN74LVC1G3157DBVR"))
    )
    (comp (ref "U7")
      (value "AX88279")
      (footprint "IC_AX88279")
      (libsource (lib "LotusSound") (part "IC_AX88279"))
    )
    (comp (ref "U9")
      (value "ST1S06PU33R")
      (footprint "DFN6D_L")
      (fields (field (name "MANUFACTURER") "STMicroelectronics"))
      (libsource (lib "Altium Content Vault") (part "PM-DCDC-ST1S06-IL7"))
    )
    (comp (ref "U10")
      (value "SST25VF016B-50-4I-QAF-T")
      (footprint "FP-C04-452-MFG")
      (libsource (lib "Altium Content Vault") (part "d7313dde12fd16fde488169701056cc"))
    )
    (comp (ref "U11")
      (value "ST1S06PUR")
      (footprint "DFN6D_M")
      (libsource (lib "Altium Content Vault") (part "PM-DCDC-ST1S06-IL7"))
    )
    (comp (ref "Y1")
      (value "25 MHz")
      (footprint "NDK NX3225GA")
      (description "CRYSTAL 25.0000MHZ 8PF SMD")
      (fields
        (field (name "MANUFACTURER") "NDK America, Inc.")
        (field (name "PART NUMBER") "NX3225GA-25.000M-STD-CRG-2")
      )
      (libsource (lib "Celestial Altium Library - altium_library") (part "NDK Crystal NX3225GA"))
    )
  )
  (nets
    (net (code "1") (name "/1PPS_IN") (class "Default")
      (node (ref "R11") (pin "1") (pinfunction "1_1") (pintype "passive"))
      (node (ref "U4") (pin "2") (pinfunction "A1_2") (pintype "passive"))
      (node (ref "U4") (pin "5") (pinfunction "A2_5") (pintype "passive"))
      (node (ref "U6") (pin "4") (pinfunction "A_4") (pintype "passive"))
    )
    (net (code "2") (name "/1PPS_IN_BUFF") (class "Default")
      (node (ref "R11") (pin "2") (pinfunction "2_2") (pintype "passive"))
      (node (ref "U2") (pin "3") (pinfunction "B1_3") (pintype "passive"))
      (node (ref "U4") (pin "3") (pinfunction "Y2_3") (pintype "passive"))
    )
    (net (code "3") (name "/1PPS_IN_LED") (class "Default")
      (node (ref "D2") (pin "1") (pinfunction "C_1") (pintype "passive"))
      (node (ref "U4") (pin "6") (pinfunction "Y1_6") (pintype "passive"))
    )
    (net (code "4") (name "/1PPS_OUT") (class "Default")
      (node (ref "R7") (pin "2") (pinfunction "2_2") (pintype "passive"))
      (node (ref "U1") (pin "2") (pinfunction "A1_2") (pintype "passive"))
      (node (ref "U1") (pin "5") (pinfunction "A2_5") (pintype "passive"))
      (node (ref "U2") (pin "1") (pinfunction "B2_1") (pintype "passive"))
    )
    (net (code "5") (name "/1PPS_OUT_BUFF") (class "Default")
      (node (ref "R7") (pin "1") (pinfunction "1_1") (pintype "passive"))
      (node (ref "U1") (pin "3") (pinfunction "Y2_3") (pintype "passive"))
      (node (ref "U3") (pin "1") (pinfunction "B2_1") (pintype "passive"))
    )
    (net (code "6") (name "/1PPS_OUT_LED") (class "Default")
      (node (ref "D1") (pin "1") (pinfunction "C_1") (pintype "passive"))
      (node (ref "U1") (pin "6") (pinfunction "Y1_6") (pintype "passive"))
    )
    (net (code "7") (name "/1PPS_SMA_IO") (class "Default")
      (node (ref "J1") (pin "1") (pinfunction "1_1") (pintype "passive"))
      (node (ref "U5") (pin "4") (pinfunction "A_4") (pintype "passive"))
    )
    (net (code "8") (name "/279_1PPS_IO") (class "Default")
      (node (ref "U2") (pin "4") (pinfunction "A_4") (pintype "passive"))
      (node (ref "U7") (pin "46") (pinfunction "GPIO14(1588_PSS)_46") (pintype "passive"))
    )
    (net (code "9") (name "/279_TOD_IN") (class "Default")
      (node (ref "IC1") (pin "2") (pinfunction "TXD_2") (pintype "passive"))
      (node (ref "IC2") (pin "20") (pinfunction "TXD_/_SPI_MISO_20") (pintype "passive"))
      (node (ref "J3") (pin "3") (pinfunction "3_3") (pintype "passive"))
      (node (ref "R23") (pin "1") (pinfunction "1_1") (pintype "passive"))
    )
    (net (code "10") (name "/279_TOD_IN_R") (class "Default")
      (node (ref "R23") (pin "2") (pinfunction "2_2") (pintype "passive"))
      (node (ref "U7") (pin "20") (pinfunction "GPIO6_20") (pintype "passive"))
    )
    (net (code "11") (name "/279_TOD_OUT") (class "Default")
      (node (ref "IC1") (pin "3") (pinfunction "RXD_3") (pintype "passive"))
      (node (ref "IC2") (pin "21") (pinfunction "RXD_/_SPI_MOSI_21") (pintype "passive"))
      (node (ref "J3") (pin "4") (pinfunction "4_4") (pintype "passive"))
      (node (ref "R26") (pin "1") (pinfunction "1_1") (pintype "passive"))
    )
    (net (code "12") (name "/279_TOD_OUT_R") (class "Default")
      (node (ref "R26") (pin "2") (pinfunction "2_2") (pintype "passive"))
      (node (ref "U7") (pin "21") (pinfunction "GPIO7_21") (pintype "passive"))
    )
    (net (code "13") (name "/ANT") (class "Default")
      (node (ref "FB1") (pin "2") (pinfunction "2_2") (pintype "passive"))
      (node (ref "IC1") (pin "11") (pinfunction "RF_IN_11") (pintype "passive"))
      (node (ref "IC2") (pin "11") (pinfunction "RF_IN_11") (pintype "passive"))
      (node (ref "J2") (pin "1") (pinfunction "1_1") (pintype "passive"))
    )
    (net (code "14") (name "/AVDD10") (class "Default")
      (node (ref "C16") (pin "2") (pinfunction "2_2") (pintype "passive"))
      (node (ref "C17") (pin "2") (pinfunction "2_2") (pintype "passive"))
      (node (ref "FB2") (pin "2") (pinfunction "2_2") (pintype "passive"))
      (node (ref "U7") (pin "43") (pinfunction "AVDD10_SSUSB_43") (pintype "passive"))
    )
    (net (code "15") (name "/AVDD_1.85") (class "Default")
      (node (ref "C39") (pin "2") (pinfunction "2_2") (pintype "passive"))
      (node (ref "C40") (pin "2") (pinfunction "2_2") (pintype "passive"))
      (node (ref "FB3") (pin "2") (pinfunction "2_2") (pintype "passive"))
      (node (ref "FB5") (pin "2") (pinfunction "2_2") (pintype "passive"))
      (node (ref "U7") (pin "40") (pinfunction "AVDD18_SSUSB_40") (pintype "passive"))
      (node (ref "U7") (pin "8") (pinfunction "AVDD18_COM_8") (pintype "passive"))
    )
    (net (code "16") (name "/AVDD_33") (class "Default")
      (node (ref "C29") (pin "2") (pinfunction "2_2") (pintype "passive"))
      (node (ref "C30") (pin "2") (pinfunction "2_2") (pintype "passive"))
      (node (ref "C31") (pin "2") (pinfunction "2_2") (pintype "passive"))
      (node (ref "C32") (pin "2") (pinfunction "2_2") (pintype "passive"))
      (node (ref "C33") (pin "2") (pinfunction "2_2") (pintype "passive"))
      (node (ref "FB4") (pin "2") (pinfunction "2_2") (pintype "passive"))
      (node (ref "U7") (pin "12") (pinfunction "AVDD33_LD_12") (pintype "passive"))
      (node (ref "U7") (pin "37") (pinfunction "GPIO13/AVD33_USB_37") (pintype "passive"))
      (node (ref "U7") (pin "5") (pinfunction "AVD33_LD_5") (pintype "passive"))
    )
    (net (code "17") (name "/DVDD_1.85") (class "Default")
      (node (ref "C22") (pin "2") (pinfunction "2_2") (pintype "passive"))
      (node (ref "C36") (pin "2") (pinfunction "2_2") (pintype "passive"))
      (node (ref "C37") (pin "2") (pinfunction "2_2") (pintype "passive"))
      (node (ref "C38") (pin "2") (pinfunction "2_2") (pintype "passive"))
      (node (ref "FB5") (pin "1") (pinfunction "1_1") (pintype "passive"))
      (node (ref "U7") (pin "26") (pinfunction "DVDD18_26") (pintype "passive"))
      (node (ref "U7") (pin "35") (pinfunction "DVDD18_35") (pintype "passive"))
      (node (ref "U7") (pin "53") (pinfunction "DVDD18_53") (pintype "passive"))
      (node (ref "U7") (pin "56") (pinfunction "LDO18_56") (pintype "passive"))
    )
    (net (code "18") (name "/D_N") (class "Default")
      (node (ref "D4") (pin "2") (pinfunction "D-_2") (pintype "passive"))
      (node (ref "J5") (pin "A7") (pinfunction "Dn1_A7") (pintype "passive"))
      (node (ref "J5") (pin "B7") (pinfunction "Dn2_B7") (pintype "passive"))
      (node (ref "U7") (pin "38") (pinfunction "GPIO12_USB_DN_38") (pintype "passive"))
    )
    (net (code "19") (name "/D_P") (class "Default")
      (node (ref "D4") (pin "1") (pinfunction "D+_1") (pintype "passive"))
      (node (ref "J5") (pin "A6") (pinfunction "Dp1_A6") (pintype "passive"))
      (node (ref "J5") (pin "B6") (pinfunction "Dp2_B6") (pintype "passive"))
      (node (ref "U7") (pin "39") (pinfunction "GPIO12_USB_DP_39") (pintype "passive"))
    )
    (net (code "20") (name "/GPS_PPS_OUT") (class "Default")
      (node (ref "IC1") (pin "4") (pinfunction "TIMEPULSE_4") (pintype "passive"))
      (node (ref "IC2") (pin "3") (pinfunction "TIMEPULSE_3") (pintype "passive"))
      (node (ref "J3") (pin "5") (pinfunction "5_5") (pintype "passive"))
      (node (ref "U5") (pin "3") (pinfunction "B1_3") (pintype "passive"))
      (node (ref "U6") (pin "3") (pinfunction "B1_3") (pintype "passive"))
    )
    (net (code "21") (name "/LED0") (class "Default")
      (node (ref "J4") (pin "12") (pinfunction "K_GREEN_12") (pintype "passive"))
      (node (ref "R18") (pin "2") (pinfunction "2_2") (pintype "passive"))
      (node (ref "U7") (pin "27") (pinfunction "GPIO5(LED0)_27") (pintype "passive"))
    )
    (net (code "22") (name "/LED1") (class "Default")
      (node (ref "J4") (pin "14") (pinfunction "K_YELLOW_14") (pintype "passive"))
      (node (ref "R19") (pin "2") (pinfunction "2_2") (pintype "passive"))
      (node (ref "U7") (pin "28") (pinfunction "GPIO4(LED1)_28") (pintype "passive"))
    )
    (net (code "23") (name "/MDI0_N") (class "Default")
      (node (ref "J4") (pin "2") (pinfunction "TD1-_2") (pintype "passive"))
      (node (ref "U7") (pin "4") (pinfunction "TXVN_A_4") (pintype "passive"))
    )
    (net (code "24") (name "/MDI0_P") (class "Default")
      (node (ref "J4") (pin "1") (pinfunction "TD1+_1") (pintype "passive"))
      (node (ref "U7") (pin "3") (pinfunction "TXVP_A_3") (pintype "passive"))
    )
    (net (code "25") (name "/MDI1_N") (class "Default")
      (node (ref "J4") (pin "4") (pinfunction "TD2-_4") (pintype "passive"))
      (node (ref "U7") (pin "7") (pinfunction "TXVP_B_7") (pintype "passive"))
    )
    (net (code "26") (name "/MDI1_P") (class "Default")
      (node (ref "J4") (pin "3") (pinfunction "TD2+_3") (pintype "passive"))
      (node (ref "U7") (pin "6") (pinfunction "TXVP_B_6") (pintype "passive"))
    )
    (net (code "27") (name "/MDI2_N") (class "Default")
      (node (ref "J4") (pin "6") (pinfunction "TD3-_6") (pintype "passive"))
      (node (ref "U7") (pin "11") (pinfunction "TXVN_C_11") (pintype "passive"))
    )
    (net (code "28") (name "/MDI2_P") (class "Default")
      (node (ref "J4") (pin "5") (pinfunction "TD3+_5") (pintype "passive"))
      (node (ref "U7") (pin "10") (pinfunction "TXVP_C_10") (pintype "passive"))
    )
    (net (code "29") (name "/MDI3_N") (class "Default")
      (node (ref "J4") (pin "8") (pinfunction "TD4-_8") (pintype "passive"))
      (node (ref "U7") (pin "14") (pinfunction "TXVN_D_14") (pintype "passive"))
    )
    (net (code "30") (name "/MDI3_P") (class "Default")
      (node (ref "J4") (pin "7") (pinfunction "TD4+_7") (pintype "passive"))
      (node (ref "U7") (pin "13") (pinfunction "TXVP_D_13") (pintype "passive"))
    )
    (net (code "31") (name "/MUX1_CTRL") (class "Default")
      (node (ref "R3") (pin "1") (pinfunction "1_1") (pintype "passive"))
      (node (ref "SW1") (pin "8") (pinfunction "8_8") (pintype "passive"))
      (node (ref "U3") (pin "6") (pinfunction "S_6") (pintype "passive"))
    )
    (net (code "32") (name "/MUX2_CTRL") (class "Default")
      (node (ref "R4") (pin "1") (pinfunction "1_1") (pintype "passive"))
      (node (ref "SW1") (pin "7") (pinfunction "7_7") (pintype "passive"))
      (node (ref "U2") (pin "6") (pinfunction "S_6") (pintype "passive"))
    )
    (net (code "33") (name "/MUX3_CTRL") (class "Default")
      (node (ref "R5") (pin "1") (pinfunction "1_1") (pintype "passive"))
      (node (ref "SW1") (pin "6") (pinfunction "6_6") (pintype "passive"))
      (node (ref "U6") (pin "6") (pinfunction "S_6") (pintype "passive"))
    )
    (net (code "34") (name "/MUX4_CTRL") (class "Default")
      (node (ref "R6") (pin "1") (pinfunction "1_1") (pintype "passive"))
      (node (ref "SW1") (pin "5") (pinfunction "5_5") (pintype "passive"))
      (node (ref "U5") (pin "6") (pinfunction "S_6") (pintype "passive"))
    )
    (net (code "35") (name "/RESET_N") (class "Default")
      (node (ref "R16") (pin "1") (pinfunction "1_1") (pintype "passive"))
      (node (ref "U7") (pin "23") (pinfunction "HW_RSTN_23") (pintype "passive"))
    )
    (net (code "36") (name "/SB") (class "Default")
      (node (ref "IC1") (pin "18") (pinfunction "SAFEBOOT_N_18") (pintype "passive"))
      (node (ref "IC2") (pin "1") (pinfunction "SAFEBOOT_N_1") (pintype "passive"))
      (node (ref "R15") (pin "1") (pinfunction "1_1") (pintype "passive"))
    )
    (net (code "37") (name "/SCL") (class "Default")
      (node (ref "IC1") (pin "17") (pinfunction "SCL_17") (pintype "passive"))
      (node (ref "IC2") (pin "19") (pinfunction "SCL_/_SPI_SLK__19") (pintype "passive"))
      (node (ref "TP2") (pin "1") (pinfunction "1_1") (pintype "passive"))
    )
    (net (code "38") (name "/SDA") (class "Default")
      (node (ref "IC1") (pin "16") (pinfunction "SDA_16") (pintype "passive"))
      (node (ref "IC2") (pin "18") (pinfunction "SDA_/_SPI_CS_N_18") (pintype "passive"))
      (node (ref "TP1") (pin "1") (pinfunction "1_1") (pintype "passive"))
    )
    (net (code "39") (name "/SPI_CLK") (class "Default")
      (node (ref "R33") (pin "2") (pinfunction "2_2") (pintype "passive"))
      (node (ref "U10") (pin "6") (pinfunction "SCK_6") (pintype "input"))
      (node (ref "U7") (pin "51") (pinfunction "SPI_CLK_51") (pintype "passive"))
    )
    (net (code "40") (name "/SPI_CS") (class "Default")
      (node (ref "R39") (pin "2") (pinfunction "2_2") (pintype "passive"))
      (node (ref "U10") (pin "1") (pinfunction "~{CE}_1") (pintype "input"))
      (node (ref "U7") (pin "50") (pinfunction "SPI_CS0_50") (pintype "passive"))
    )
    (net (code "41") (name "/SPI_DIO") (class "Default")
      (node (ref "R32") (pin "2") (pinfunction "2_2") (pintype "passive"))
      (node (ref "R36") (pin "2") (pinfunction "2_2") (pintype "passive"))
      (node (ref "U10") (pin "5") (pinfunction "SI_5") (pintype "input"))
      (node (ref "U7") (pin "52") (pinfunction "SPI_DIO_52") (pintype "passive"))
    )
    (net (code "42") (name "/SSRX_N") (class "Default")
      (node (ref "D5") (pin "2") (pinfunction "D-_2") (pintype "passive"))
      (node (ref "J5") (pin "A10") (pinfunction "SSRXn2_A10") (pintype "passive"))
      (node (ref "J5") (pin "B10") (pinfunction "SSRXn1_B10") (pintype "passive"))
      (node (ref "U7") (pin "44") (pinfunction "SSUSBRXN_44") (pintype "passive"))
    )
    (net (code "43") (name "/SSRX_P") (class "Default")
      (node (ref "D5") (pin "1") (pinfunction "D+_1") (pintype "passive"))
      (node (ref "J5") (pin "A11") (pinfunction "SSRXp2_A11") (pintype "passive"))
      (node (ref "J5") (pin "B11") (pinfunction "SSRXp1_B11") (pintype "passive"))
      (node (ref "U7") (pin "45") (pinfunction "SSUSBRXP_45") (pintype "passive"))
    )
    (net (code "44") (name "/SSTX_N") (class "Default")
      (node (ref "C11") (pin "2") (pinfunction "2_2") (pintype "passive"))
      (node (ref "D3") (pin "2") (pinfunction "D-_2") (pintype "passive"))
      (node (ref "U7") (pin "41") (pinfunction "SSUSB_TXN_41") (pintype "passive"))
    )
    (net (code "45") (name "/SSTX_P") (class "Default")
      (node (ref "C10") (pin "2") (pinfunction "2_2") (pintype "passive"))
      (node (ref "D3") (pin "1") (pinfunction "D+_1") (pintype "passive"))
      (node (ref "U7") (pin "42") (pinfunction "SSUSB_TXP_42") (pintype "passive"))
    )
    (net (code "46") (name "/USB3.0_SSTX_N") (class "Default")
      (node (ref "C11") (pin "1") (pinfunction "1_1") (pintype "passive"))
      (node (ref "J5") (pin "A3") (pinfunction "SSTXn1_A3") (pintype "passive"))
      (node (ref "J5") (pin "B3") (pinfunction "SSTXn2_B3") (pintype "passive"))
    )
    (net (code "47") (name "/USB3.0_SSTX_P") (class "Default")
      (node (ref "C10") (pin "1") (pinfunction "1_1") (pintype "passive"))
      (node (ref "J5") (pin "A2") (pinfunction "SSTXp1_A2") (pintype "passive"))
      (node (ref "J5") (pin "B2") (pinfunction "SSTXp2_B2") (pintype "passive"))
    )
    (net (code "48") (name "/VBUS") (class "Default")
      (node (ref "R14") (pin "1") (pinfunction "1_1") (pintype "passive"))
      (node (ref "R17") (pin "2") (pinfunction "2_2") (pintype "passive"))
      (node (ref "U7") (pin "34") (pinfunction "GPIO9(VBUS)_34") (pintype "passive"))
    )
    (net (code "49") (name "/VCC_RF") (class "Default")
      (node (ref "IC1") (pin "14") (pinfunction "VCC_RF_14") (pintype "passive"))
      (node (ref "IC2") (pin "9") (pinfunction "VCC_RF_9") (pintype "passive"))
      (node (ref "R20") (pin "1") (pinfunction "1_1") (pintype "passive"))
    )
    (net (code "50") (name "/VCORE_LDO") (class "Default")
      (node (ref "C21") (pin "2") (pinfunction "2_2") (pintype "passive"))
      (node (ref "FB2") (pin "1") (pinfunction "1_1") (pintype "passive"))
      (node (ref "U7") (pin "55") (pinfunction "VCORE_LDO_55") (pintype "passive"))
    )
    (net (code "51") (name "/XTL20N") (class "Default")
      (node (ref "R28") (pin "2") (pinfunction "2_2") (pintype "passive"))
      (node (ref "U7") (pin "16") (pinfunction "XTAL_XO_16") (pintype "passive"))
    )
    (net (code "52") (name "/XTL20P") (class "Default")
      (node (ref "R27") (pin "2") (pinfunction "2_2") (pintype "passive"))
      (node (ref "U7") (pin "17") (pinfunction "XTAL_IN_17") (pintype "passive"))
    )
    (net (code "53") (name "CHASSIS_GND") (class "Default")
      (node (ref "C9") (pin "1") (pinfunction "1_1") (pintype "passive"))
      (node (ref "J4") (pin "15") (pinfunction "MH1_15") (pintype "passive"))
      (node (ref "J4") (pin "16") (pinfunction "MH2_16") (pintype "passive"))
      (node (ref "R13") (pin "1") (pinfunction "1_1") (pintype "passive"))
    )
    (net (code "54") (name "DVDD_33") (class "Default")
      (node (ref "C18") (pin "2") (pinfunction "2_2") (pintype "passive"))
      (node (ref "C19") (pin "2") (pinfunction "2_2") (pintype "passive"))
      (node (ref "C25") (pin "2") (pinfunction "2_2") (pintype "passive"))
      (node (ref "C26") (pin "2") (pinfunction "2_2") (pintype "passive"))
      (node (ref "C27") (pin "2") (pinfunction "2_2") (pintype "passive"))
      (node (ref "C28") (pin "2") (pinfunction "2_2") (pintype "passive"))
      (node (ref "C7") (pin "2") (pinfunction "2_2") (pintype "passive"))
      (node (ref "C8") (pin "2") (pinfunction "2_2") (pintype "passive"))
      (node (ref "FB4") (pin "1") (pinfunction "1_1") (pintype "passive"))
      (node (ref "IC1") (pin "7") (pinfunction "V_IO_7") (pintype "passive"))
      (node (ref "IC1") (pin "8") (pinfunction "VCC_8") (pintype "passive"))
      (node (ref "IC2") (pin "2") (pinfunction "D_SEL_2") (pintype "passive"))
      (node (ref "IC2") (pin "23") (pinfunction "VCC_23") (pintype "passive"))
      (node (ref "IC2") (pin "7") (pinfunction "V_USB_7") (pintype "passive"))
      (node (ref "L1") (pin "2") (pinfunction "2_2") (pintype "passive"))
      (node (ref "R10") (pin "2") (pinfunction "2_2") (pintype "passive"))
      (node (ref "R12") (pin "2") (pinfunction "2_2") (pintype "passive"))
      (node (ref "R16") (pin "2") (pinfunction "2_2") (pintype "passive"))
      (node (ref "R18") (pin "1") (pinfunction "1_1") (pintype "passive"))
      (node (ref "R19") (pin "1") (pinfunction "1_1") (pintype "passive"))
      (node (ref "R22") (pin "2") (pinfunction "2_2") (pintype "passive"))
      (node (ref "R24") (pin "2") (pinfunction "2_2") (pintype "passive"))
      (node (ref "R25") (pin "2") (pinfunction "2_2") (pintype "passive"))
      (node (ref "R32") (pin "1") (pinfunction "1_1") (pintype "passive"))
      (node (ref "R33") (pin "1") (pinfunction "1_1") (pintype "passive"))
      (node (ref "R34") (pin "1") (pinfunction "1_1") (pintype "passive"))
      (node (ref "R35") (pin "1") (pinfunction "1_1") (pintype "passive"))
      (node (ref "R39") (pin "1") (pinfunction "1_1") (pintype "passive"))
      (node (ref "U10") (pin "8") (pinfunction "VDD_8") (pintype "power_in"))
      (node (ref "U7") (pin "25") (pinfunction "DVDD33_25") (pintype "passive"))
      (node (ref "U7") (pin "36") (pinfunction "DVDD33_36") (pintype "passive"))
      (node (ref "U7") (pin "54") (pinfunction "AVDD33_LDO_54") (pintype "passive"))
      (node (ref "U7") (pin "59") (pinfunction "AVD33_BUCK_59") (pintype "passive"))
      (node (ref "U9") (pin "1") (pinfunction "VO/VFB_1") (pintype "bidirectional"))
    )
    (net (code "55") (name "GND") (class "Default")
      (node (ref "C1") (pin "1") (pinfunction "1_1") (pintype "passive"))
      (node (ref "C12") (pin "1") (pinfunction "1_1") (pintype "passive"))
      (node (ref "C13") (pin "1") (pinfunction "1_1") (pintype "passive"))
      (node (ref "C14") (pin "1") (pinfunction "1_1") (pintype "passive"))
      (node (ref "C15") (pin "1") (pinfunction "1_1") (pintype "passive"))
      (node (ref "C16") (pin "1") (pinfunction "1_1") (pintype "passive"))
      (node (ref "C17") (pin "1") (pinfunction "1_1") (pintype "passive"))
      (node (ref "C18") (pin "1") (pinfunction "1_1") (pintype "passive"))
      (node (ref "C19") (pin "1") (pinfunction "1_1") (pintype "passive"))
      (node (ref "C2") (pin "1") (pinfunction "1_1") (pintype "passive"))
      (node (ref "C20") (pin "1") (pinfunction "1_1") (pintype "passive"))
      (node (ref "C21") (pin "1") (pinfunction "1_1") (pintype "passive"))
      (node (ref "C22") (pin "1") (pinfunction "1_1") (pintype "passive"))
      (node (ref "C23") (pin "1") (pinfunction "1_1") (pintype "passive"))
      (node (ref "C24") (pin "1") (pinfunction "1_1") (pintype "passive"))
      (node (ref "C25") (pin "1") (pinfunction "1_1") (pintype "passive"))
      (node (ref "C26") (pin "1") (pinfunction "1_1") (pintype "passive"))
      (node (ref "C27") (pin "1") (pinfunction "1_1") (pintype "passive"))
      (node (ref "C28") (pin "1") (pinfunction "1_1") (pintype "passive"))
      (node (ref "C29") (pin "1") (pinfunction "1_1") (pintype "passive"))
      (node (ref "C3") (pin "1") (pinfunction "1_1") (pintype "passive"))
      (node (ref "C30") (pin "1") (pinfunction "1_1") (pintype "passive"))
      (node (ref "C31") (pin "1") (pinfunction "1_1") (pintype "passive"))
      (node (ref "C32") (pin "1") (pinfunction "1_1") (pintype "passive"))
      (node (ref "C33") (pin "1") (pinfunction "1_1") (pintype "passive"))
      (node (ref "C34") (pin "1") (pinfunction "1_1") (pintype "passive"))
      (node (ref "C35") (pin "1") (pinfunction "1_1") (pintype "passive"))
      (node (ref "C36") (pin "1") (pinfunction "1_1") (pintype "passive"))
      (node (ref "C37") (pin "1") (pinfunction "1_1") (pintype "passive"))
      (node (ref "C38") (pin "1") (pinfunction "1_1") (pintype "passive"))
      (node (ref "C39") (pin "1") (pinfunction "1_1") (pintype "passive"))
      (node (ref "C4") (pin "1") (pinfunction "1_1") (pintype "passive"))
      (node (ref "C40") (pin "1") (pinfunction "1_1") (pintype "passive"))
      (node (ref "C41") (pin "1") (pinfunction "1_1") (pintype "passive"))
      (node (ref "C42") (pin "1") (pinfunction "1_1") (pintype "passive"))
      (node (ref "C43") (pin "1") (pinfunction "1_1") (pintype "passive"))
      (node (ref "C44") (pin "1") (pinfunction "1_1") (pintype "passive"))
      (node (ref "C5") (pin "1") (pinfunction "1_1") (pintype "passive"))
      (node (ref "C6") (pin "1") (pinfunction "1_1") (pintype "passive"))
      (node (ref "C7") (pin "1") (pinfunction "1_1") (pintype "passive"))
      (node (ref "C8") (pin "1") (pinfunction "1_1") (pintype "passive"))
      (node (ref "C9") (pin "2") (pinfunction "2_2") (pintype "passive"))
      (node (ref "D3") (pin "3") (pinfunction "GND_3") (pintype "passive"))
      (node (ref "D4") (pin "3") (pinfunction "GND_3") (pintype "passive"))
      (node (ref "D5") (pin "3") (pinfunction "GND_3") (pintype "passive"))
      (node (ref "IC1") (pin "1") (pinfunction "GND_1_1") (pintype "passive"))
      (node (ref "IC1") (pin "10") (pinfunction "GND_2_10") (pintype "passive"))
      (node (ref "IC1") (pin "12") (pinfunction "GND_3_12") (pintype "passive"))
      (node (ref "IC2") (pin "10") (pinfunction "GND_1_10") (pintype "passive"))
      (node (ref "IC2") (pin "12") (pinfunction "GND_2_12") (pintype "passive"))
      (node (ref "IC2") (pin "13") (pinfunction "GND_3_13") (pintype "passive"))
      (node (ref "IC2") (pin "24") (pinfunction "GND_4_24") (pintype "passive"))
      (node (ref "J1") (pin "2") (pinfunction "2_2") (pintype "passive"))
      (node (ref "J1") (pin "3") (pinfunction "3_3") (pintype "passive"))
      (node (ref "J1") (pin "4") (pinfunction "4_4") (pintype "passive"))
      (node (ref "J1") (pin "5") (pinfunction "5_5") (pintype "passive"))
      (node (ref "J2") (pin "2") (pinfunction "2_2") (pintype "passive"))
      (node (ref "J2") (pin "3") (pinfunction "3_3") (pintype "passive"))
      (node (ref "J2") (pin "4") (pinfunction "4_4") (pintype "passive"))
      (node (ref "J2") (pin "5") (pinfunction "5_5") (pintype "passive"))
      (node (ref "J3") (pin "1") (pinfunction "1_1") (pintype "passive"))
      (node (ref "J4") (pin "10") (pinfunction "GND_10") (pintype "passive"))
      (node (ref "J5") (pin "A1") (pinfunction "GND_A1") (pintype "passive"))
      (node (ref "J5") (pin "A12") (pinfunction "GND_A12") (pintype "passive"))
      (node (ref "J5") (pin "B1") (pinfunction "GND_B1") (pintype "passive"))
      (node (ref "J5") (pin "B12") (pinfunction "GND_B12") (pintype "passive"))
      (node (ref "R1") (pin "2") (pinfunction "2_2") (pintype "passive"))
      (node (ref "R13") (pin "2") (pinfunction "2_2") (pintype "passive"))
      (node (ref "R15") (pin "2") (pinfunction "2_2") (pintype "passive"))
      (node (ref "R17") (pin "1") (pinfunction "1_1") (pintype "passive"))
      (node (ref "R21") (pin "1") (pinfunction "1_1") (pintype "passive"))
      (node (ref "R29") (pin "2") (pinfunction "2_2") (pintype "passive"))
      (node (ref "R30") (pin "1") (pinfunction "1_1") (pintype "passive"))
      (node (ref "R31") (pin "2") (pinfunction "2_2") (pintype "passive"))
      (node (ref "R38") (pin "2") (pinfunction "2_2") (pintype "passive"))
      (node (ref "R8") (pin "1") (pinfunction "1_1") (pintype "passive"))
      (node (ref "SW1") (pin "1") (pinfunction "GND_1") (pintype "passive"))
      (node (ref "SW1") (pin "2") (pinfunction "GND_2") (pintype "passive"))
      (node (ref "SW1") (pin "3") (pinfunction "GND_3") (pintype "passive"))
      (node (ref "SW1") (pin "4") (pinfunction "GND_4") (pintype "passive"))
      (node (ref "U1") (pin "4") (pinfunction "GND_4") (pintype "passive"))
      (node (ref "U10") (pin "4") (pinfunction "VSS_4") (pintype "power_in"))
      (node (ref "U10") (pin "9") (pinfunction "VSS_9") (pintype "power_in"))
      (node (ref "U11") (pin "2") (pinfunction "GND_2") (pintype "power_in"))
      (node (ref "U11") (pin "7") (pinfunction "Thermal_Pad_7") (pintype "power_in"))
      (node (ref "U2") (pin "2") (pinfunction "GND_2") (pintype "passive"))
      (node (ref "U3") (pin "2") (pinfunction "GND_2") (pintype "passive"))
      (node (ref "U4") (pin "4") (pinfunction "GND_4") (pintype "passive"))
      (node (ref "U5") (pin "2") (pinfunction "GND_2") (pintype "passive"))
      (node (ref "U6") (pin "2") (pinfunction "GND_2") (pintype "passive"))
      (node (ref "U7") (pin "1") (pinfunction "AVSS33_BUCK_1") (pintype "passive"))
      (node (ref "U7") (pin "2") (pinfunction "AVSS33_BUCK_2") (pintype "passive"))
      (node (ref "U7") (pin "61") (pinfunction "E_PAD_61") (pintype "passive"))
      (node (ref "U9") (pin "2") (pinfunction "GND_2") (pintype "power_in"))
      (node (ref "U9") (pin "7") (pinfunction "Thermal_Pad_7") (pintype "power_in"))
      (node (ref "Y1") (pin "2") (pinfunction "GND_2") (pintype "passive"))
      (node (ref "Y1") (pin "4") (pinfunction "GND_4") (pintype "passive"))
    )
    (net (code "56") (name "Net-(C12-Pad2)") (class "Default")
      (node (ref "C12") (pin "2") (pinfunction "2_2") (pintype "passive"))
      (node (ref "FB1") (pin "1") (pinfunction "1_1") (pintype "passive"))
      (node (ref "R20") (pin "2") (pinfunction "2_2") (pintype "passive"))
    )
    (net (code "57") (name "Net-(C13-Pad2)") (class "Default")
      (node (ref "C13") (pin "2") (pinfunction "2_2") (pintype "passive"))
      (node (ref "R27") (pin "1") (pinfunction "1_1") (pintype "passive"))
      (node (ref "Y1") (pin "1") (pinfunction "1_1") (pintype "passive"))
    )
    (net (code "58") (name "Net-(C14-Pad2)") (class "Default")
      (node (ref "C14") (pin "2") (pinfunction "2_2") (pintype "passive"))
      (node (ref "R28") (pin "1") (pinfunction "1_1") (pintype "passive"))
      (node (ref "Y1") (pin "3") (pinfunction "3_3") (pintype "passive"))
    )
    (net (code "59") (name "Net-(D1-A)") (class "Default")
      (node (ref "D1") (pin "2") (pinfunction "A_2") (pintype "passive"))
      (node (ref "R2") (pin "1") (pinfunction "1_1") (pintype "passive"))
    )
    (net (code "60") (name "Net-(D2-A)") (class "Default")
      (node (ref "D2") (pin "2") (pinfunction "A_2") (pintype "passive"))
      (node (ref "R9") (pin "1") (pinfunction "1_1") (pintype "passive"))
    )
    (net (code "61") (name "Net-(J4-A_GREEN)") (class "Default")
      (node (ref "J4") (pin "11") (pinfunction "A_GREEN_11") (pintype "passive"))
      (node (ref "R10") (pin "1") (pinfunction "1_1") (pintype "passive"))
    )
    (net (code "62") (name "Net-(J4-A_YELLOW)") (class "Default")
      (node (ref "J4") (pin "13") (pinfunction "A_YELLOW_13") (pintype "passive"))
      (node (ref "R12") (pin "1") (pinfunction "1_1") (pintype "passive"))
    )
    (net (code "63") (name "Net-(J5-CC1)") (class "Default")
      (node (ref "J5") (pin "A5") (pinfunction "CC1_A5") (pintype "passive"))
      (node (ref "R29") (pin "1") (pinfunction "1_1") (pintype "passive"))
    )
    (net (code "64") (name "Net-(J5-CC2)") (class "Default")
      (node (ref "J5") (pin "B5") (pinfunction "CC2_B5") (pintype "passive"))
      (node (ref "R31") (pin "1") (pinfunction "1_1") (pintype "passive"))
    )
    (net (code "65") (name "Net-(J5-Shield)") (class "Default")
      (node (ref "C15") (pin "2") (pinfunction "2_2") (pintype "passive"))
      (node (ref "J5") (pin "S") (pinfunction "Shield_S") (pintype "passive"))
      (node (ref "R30") (pin "2") (pinfunction "2_2") (pintype "passive"))
    )
    (net (code "66") (name "Net-(U1-~{OE1})") (class "Default")
      (node (ref "R1") (pin "1") (pinfunction "1_1") (pintype "passive"))
      (node (ref "U1") (pin "1") (pinfunction "~{OE1}_1") (pintype "passive"))
      (node (ref "U1") (pin "7") (pinfunction "~{OE2}_7") (pintype "passive"))
    )
    (net (code "67") (name "Net-(U3-A)") (class "Default")
      (node (ref "U3") (pin "4") (pinfunction "A_4") (pintype "passive"))
      (node (ref "U5") (pin "1") (pinfunction "B2_1") (pintype "passive"))
    )
    (net (code "68") (name "Net-(U3-B1)") (class "Default")
      (node (ref "U3") (pin "3") (pinfunction "B1_3") (pintype "passive"))
      (node (ref "U6") (pin "1") (pinfunction "B2_1") (pintype "passive"))
    )
    (net (code "69") (name "Net-(U4-~{OE1})") (class "Default")
      (node (ref "R8") (pin "2") (pinfunction "2_2") (pintype "passive"))
      (node (ref "U4") (pin "1") (pinfunction "~{OE1}_1") (pintype "passive"))
      (node (ref "U4") (pin "7") (pinfunction "~{OE2}_7") (pintype "passive"))
    )
    (net (code "70") (name "Net-(U7-AVDD18_XTAL)") (class "Default")
      (node (ref "C23") (pin "2") (pinfunction "2_2") (pintype "passive"))
      (node (ref "C24") (pin "2") (pinfunction "2_2") (pintype "passive"))
      (node (ref "FB3") (pin "1") (pinfunction "1_1") (pintype "passive"))
      (node (ref "U7") (pin "15") (pinfunction "AVDD18_XTAL_15") (pintype "passive"))
    )
    (net (code "71") (name "Net-(U7-GPIO3(LED2))") (class "Default")
      (node (ref "R22") (pin "1") (pinfunction "1_1") (pintype "passive"))
      (node (ref "U7") (pin "29") (pinfunction "GPIO3(LED2)_29") (pintype "passive"))
    )
    (net (code "72") (name "Net-(U7-GPIO8(WAKEUP_B))") (class "Default")
      (node (ref "R25") (pin "1") (pinfunction "1_1") (pintype "passive"))
      (node (ref "U7") (pin "33") (pinfunction "GPIO8(WAKEUP_B)_33") (pintype "passive"))
    )
    (net (code "73") (name "Net-(U7-GPIO10(SYNCE_LOCK))") (class "Default")
      (node (ref "R24") (pin "1") (pinfunction "1_1") (pintype "passive"))
      (node (ref "U7") (pin "19") (pinfunction "GPIO10(SYNCE_LOCK)_19") (pintype "passive"))
    )
    (net (code "74") (name "Net-(U7-MPXP)") (class "Default")
      (node (ref "R21") (pin "2") (pinfunction "2_2") (pintype "passive"))
      (node (ref "U7") (pin "9") (pinfunction "MPXP_9") (pintype "passive"))
    )
    (net (code "75") (name "Net-(U9-SW)") (class "Default")
      (node (ref "L1") (pin "1") (pinfunction "1_1") (pintype "passive"))
      (node (ref "U9") (pin "3") (pinfunction "SW_3") (pintype "passive"))
    )
    (net (code "76") (name "Net-(U10-SO)") (class "Default")
      (node (ref "R36") (pin "1") (pinfunction "1_1") (pintype "passive"))
      (node (ref "U10") (pin "2") (pinfunction "SO_2") (pintype "output"))
    )
    (net (code "77") (name "Net-(U10-~{HOLD})") (class "Default")
      (node (ref "R34") (pin "2") (pinfunction "2_2") (pintype "passive"))
      (node (ref "U10") (pin "7") (pinfunction "~{HOLD}_7") (pintype "input"))
    )
    (net (code "78") (name "Net-(U10-~{WP})") (class "Default")
      (node (ref "R35") (pin "2") (pinfunction "2_2") (pintype "passive"))
      (node (ref "U10") (pin "3") (pinfunction "~{WP}_3") (pintype "input"))
    )
    (net (code "79") (name "Net-(U11-SW)") (class "Default")
      (node (ref "L2") (pin "1") (pinfunction "1_1") (pintype "passive"))
      (node (ref "U11") (pin "3") (pinfunction "SW_3") (pintype "passive"))
    )
    (net (code "80") (name "Net-(U11-VO{slash}VFB)") (class "Default")
      (node (ref "R37") (pin "2") (pinfunction "2_2") (pintype "passive"))
      (node (ref "R38") (pin "1") (pinfunction "1_1") (pintype "passive"))
      (node (ref "U11") (pin "1") (pinfunction "VO/VFB_1") (pintype "bidirectional"))
    )
    (net (code "81") (name "VBUS_+5V") (class "Default")
      (node (ref "C1") (pin "2") (pinfunction "2_2") (pintype "passive"))
      (node (ref "C2") (pin "2") (pinfunction "2_2") (pintype "passive"))
      (node (ref "C20") (pin "2") (pinfunction "2_2") (pintype "passive"))
      (node (ref "C3") (pin "2") (pinfunction "2_2") (pintype "passive"))
      (node (ref "C35") (pin "2") (pinfunction "2_2") (pintype "passive"))
      (node (ref "C4") (pin "2") (pinfunction "2_2") (pintype "passive"))
      (node (ref "C5") (pin "2") (pinfunction "2_2") (pintype "passive"))
      (node (ref "C6") (pin "2") (pinfunction "2_2") (pintype "passive"))
      (node (ref "J3") (pin "2") (pinfunction "2_2") (pintype "passive"))
      (node (ref "J5") (pin "A4") (pinfunction "VBUS_A4") (pintype "passive"))
      (node (ref "J5") (pin "A9") (pinfunction "VBUS_A9") (pintype "passive"))
      (node (ref "J5") (pin "B4") (pinfunction "VBUS_B4") (pintype "passive"))
      (node (ref "J5") (pin "B9") (pinfunction "VBUS_B9") (pintype "passive"))
      (node (ref "R14") (pin "2") (pinfunction "2_2") (pintype "passive"))
      (node (ref "R2") (pin "2") (pinfunction "2_2") (pintype "passive"))
      (node (ref "R3") (pin "2") (pinfunction "2_2") (pintype "passive"))
      (node (ref "R4") (pin "2") (pinfunction "2_2") (pintype "passive"))
      (node (ref "R5") (pin "2") (pinfunction "2_2") (pintype "passive"))
      (node (ref "R6") (pin "2") (pinfunction "2_2") (pintype "passive"))
      (node (ref "R9") (pin "2") (pinfunction "2_2") (pintype "passive"))
      (node (ref "U1") (pin "8") (pinfunction "VCC_8") (pintype "passive"))
      (node (ref "U11") (pin "4") (pinfunction "VIN_SW_4") (pintype "input"))
      (node (ref "U11") (pin "5") (pinfunction "VIN_A_5") (pintype "input"))
      (node (ref "U11") (pin "6") (pinfunction "VINH_6") (pintype "input"))
      (node (ref "U2") (pin "5") (pinfunction "VCC_5") (pintype "passive"))
      (node (ref "U3") (pin "5") (pinfunction "VCC_5") (pintype "passive"))
      (node (ref "U4") (pin "8") (pinfunction "VCC_8") (pintype "passive"))
      (node (ref "U5") (pin "5") (pinfunction "VCC_5") (pintype "passive"))
      (node (ref "U6") (pin "5") (pinfunction "VCC_5") (pintype "passive"))
      (node (ref "U9") (pin "4") (pinfunction "VIN_SW_4") (pintype "input"))
      (node (ref "U9") (pin "5") (pinfunction "VIN_A_5") (pintype "input"))
      (node (ref "U9") (pin "6") (pinfunction "VINH_6") (pintype "input"))
    )
    (net (code "82") (name "VCCK10") (class "Default")
      (node (ref "C34") (pin "2") (pinfunction "2_2") (pintype "passive"))
      (node (ref "C41") (pin "2") (pinfunction "2_2") (pintype "passive"))
      (node (ref "C42") (pin "2") (pinfunction "2_2") (pintype "passive"))
      (node (ref "C43") (pin "2") (pinfunction "2_2") (pintype "passive"))
      (node (ref "C44") (pin "2") (pinfunction "2_2") (pintype "passive"))
      (node (ref "L2") (pin "2") (pinfunction "2_2") (pintype "passive"))
      (node (ref "R37") (pin "1") (pinfunction "1_1") (pintype "passive"))
      (node (ref "U7") (pin "24") (pinfunction "VCCK_24") (pintype "passive"))
      (node (ref "U7") (pin "30") (pinfunction "VCCK_30") (pintype "passive"))
      (node (ref "U7") (pin "31") (pinfunction "VCCK_31") (pintype "passive"))
      (node (ref "U7") (pin "32") (pinfunction "VCCK_32") (pintype "passive"))
      (node (ref "U7") (pin "57") (pinfunction "VCCK_57") (pintype "passive"))
      (node (ref "U7") (pin "58") (pinfunction "VCCK_58") (pintype "passive"))
    )
    (net (code "83") (name "unconnected-(IC1-EXTINT-Pad5)") (class "Default")
      (node (ref "IC1") (pin "5") (pinfunction "EXTINT_5") (pintype "passive+no_connect"))
    )
    (net (code "84") (name "unconnected-(IC1-LNA_EN-Pad13)") (class "Default")
      (node (ref "IC1") (pin "13") (pinfunction "LNA_EN_13") (pintype "passive+no_connect"))
    )
    (net (code "85") (name "unconnected-(IC1-RESET_N-Pad9)") (class "Default")
      (node (ref "IC1") (pin "9") (pinfunction "RESET_N_9") (pintype "passive+no_connect"))
    )
    (net (code "86") (name "unconnected-(IC1-VIO_SEL-Pad15)") (class "Default")
      (node (ref "IC1") (pin "15") (pinfunction "VIO_SEL_15") (pintype "passive+no_connect"))
    )
    (net (code "87") (name "unconnected-(IC1-V_BCKP-Pad6)") (class "Default")
      (node (ref "IC1") (pin "6") (pinfunction "V_BCKP_6") (pintype "passive+no_connect"))
    )
    (net (code "88") (name "unconnected-(IC2-EXTINT-Pad4)") (class "Default")
      (node (ref "IC2") (pin "4") (pinfunction "EXTINT_4") (pintype "passive+no_connect"))
    )
    (net (code "89") (name "unconnected-(IC2-LNA_EN-Pad14)") (class "Default")
      (node (ref "IC2") (pin "14") (pinfunction "LNA_EN_14") (pintype "passive+no_connect"))
    )
    (net (code "90") (name "unconnected-(IC2-RESERVED_1-Pad15)") (class "Default")
      (node (ref "IC2") (pin "15") (pinfunction "RESERVED_1_15") (pintype "passive+no_connect"))
    )
    (net (code "91") (name "unconnected-(IC2-RESERVED_2-Pad16)") (class "Default")
      (node (ref "IC2") (pin "16") (pinfunction "RESERVED_2_16") (pintype "passive+no_connect"))
    )
    (net (code "92") (name "unconnected-(IC2-RESERVED_3-Pad17)") (class "Default")
      (node (ref "IC2") (pin "17") (pinfunction "RESERVED_3_17") (pintype "passive+no_connect"))
    )
    (net (code "93") (name "unconnected-(IC2-RESET_N-Pad8)") (class "Default")
      (node (ref "IC2") (pin "8") (pinfunction "RESET_N_8") (pintype "passive+no_connect"))
    )
    (net (code "94") (name "unconnected-(IC2-USB_DM-Pad5)") (class "Default")
      (node (ref "IC2") (pin "5") (pinfunction "USB_DM_5") (pintype "passive+no_connect"))
    )
    (net (code "95") (name "unconnected-(IC2-USB_DP-Pad6)") (class "Default")
      (node (ref "IC2") (pin "6") (pinfunction "USB_DP_6") (pintype "passive+no_connect"))
    )
    (net (code "96") (name "unconnected-(IC2-V_BCKP-Pad22)") (class "Default")
      (node (ref "IC2") (pin "22") (pinfunction "V_BCKP_22") (pintype "passive+no_connect"))
    )
    (net (code "97") (name "unconnected-(J4-VCC-Pad9)") (class "Default")
      (node (ref "J4") (pin "9") (pinfunction "VCC_9") (pintype "passive+no_connect"))
    )
    (net (code "98") (name "unconnected-(J5-SBU1-PadA8)") (class "Default")
      (node (ref "J5") (pin "A8") (pinfunction "SBU1_A8") (pintype "passive+no_connect"))
    )
    (net (code "99") (name "unconnected-(J5-SBU2-PadB8)") (class "Default")
      (node (ref "J5") (pin "B8") (pinfunction "SBU2_B8") (pintype "passive+no_connect"))
    )
    (net (code "100") (name "unconnected-(U7-CKO-Pad18)") (class "Default")
      (node (ref "U7") (pin "18") (pinfunction "CKO_18") (pintype "passive+no_connect"))
    )
    (net (code "101") (name "unconnected-(U7-GPIO0(MDC)-Pad48)") (class "Default")
      (node (ref "U7") (pin "48") (pinfunction "GPIO0(MDC)_48") (pintype "passive+no_connect"))
    )
    (net (code "102") (name "unconnected-(U7-GPIO1(MDIO)-Pad49)") (class "Default")
      (node (ref "U7") (pin "49") (pinfunction "GPIO1(MDIO)_49") (pintype "passive+no_connect"))
    )
    (net (code "103") (name "unconnected-(U7-GPIO2-Pad22)") (class "Default")
      (node (ref "U7") (pin "22") (pinfunction "GPIO2_22") (pintype "passive+no_connect"))
    )
    (net (code "104") (name "unconnected-(U7-GPIO15(1588_TOD)-Pad47)") (class "Default")
      (node (ref "U7") (pin "47") (pinfunction "GPIO15(1588_TOD)_47") (pintype "passive+no_connect"))
    )
    (net (code "105") (name "unconnected-(U7-LX-Pad60)") (class "Default")
      (node (ref "U7") (pin "60") (pinfunction "LX_60") (pintype "passive+no_connect"))
    )
  )
)
